# speedy_bldc.net
KiCad netlist of a schematic drawn in EAGLE
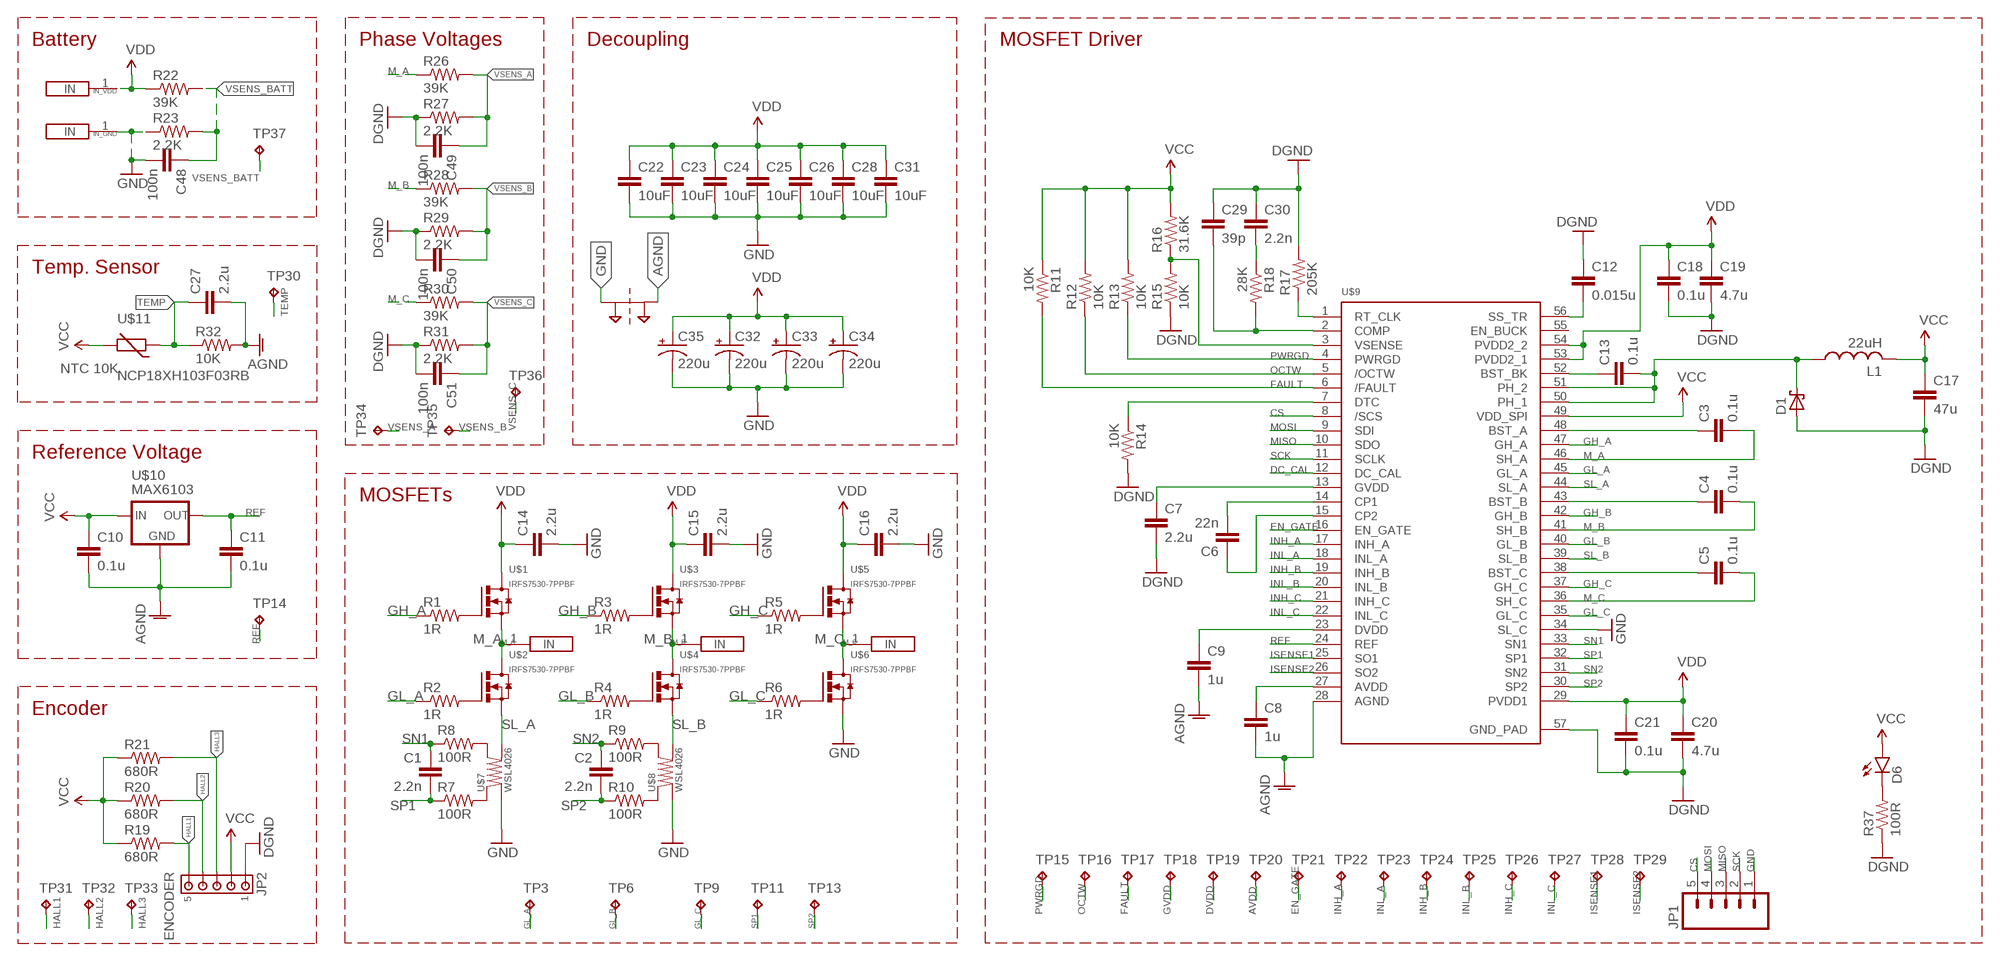
[diagram p0: schematic, sheet 1, part 1 of 2]
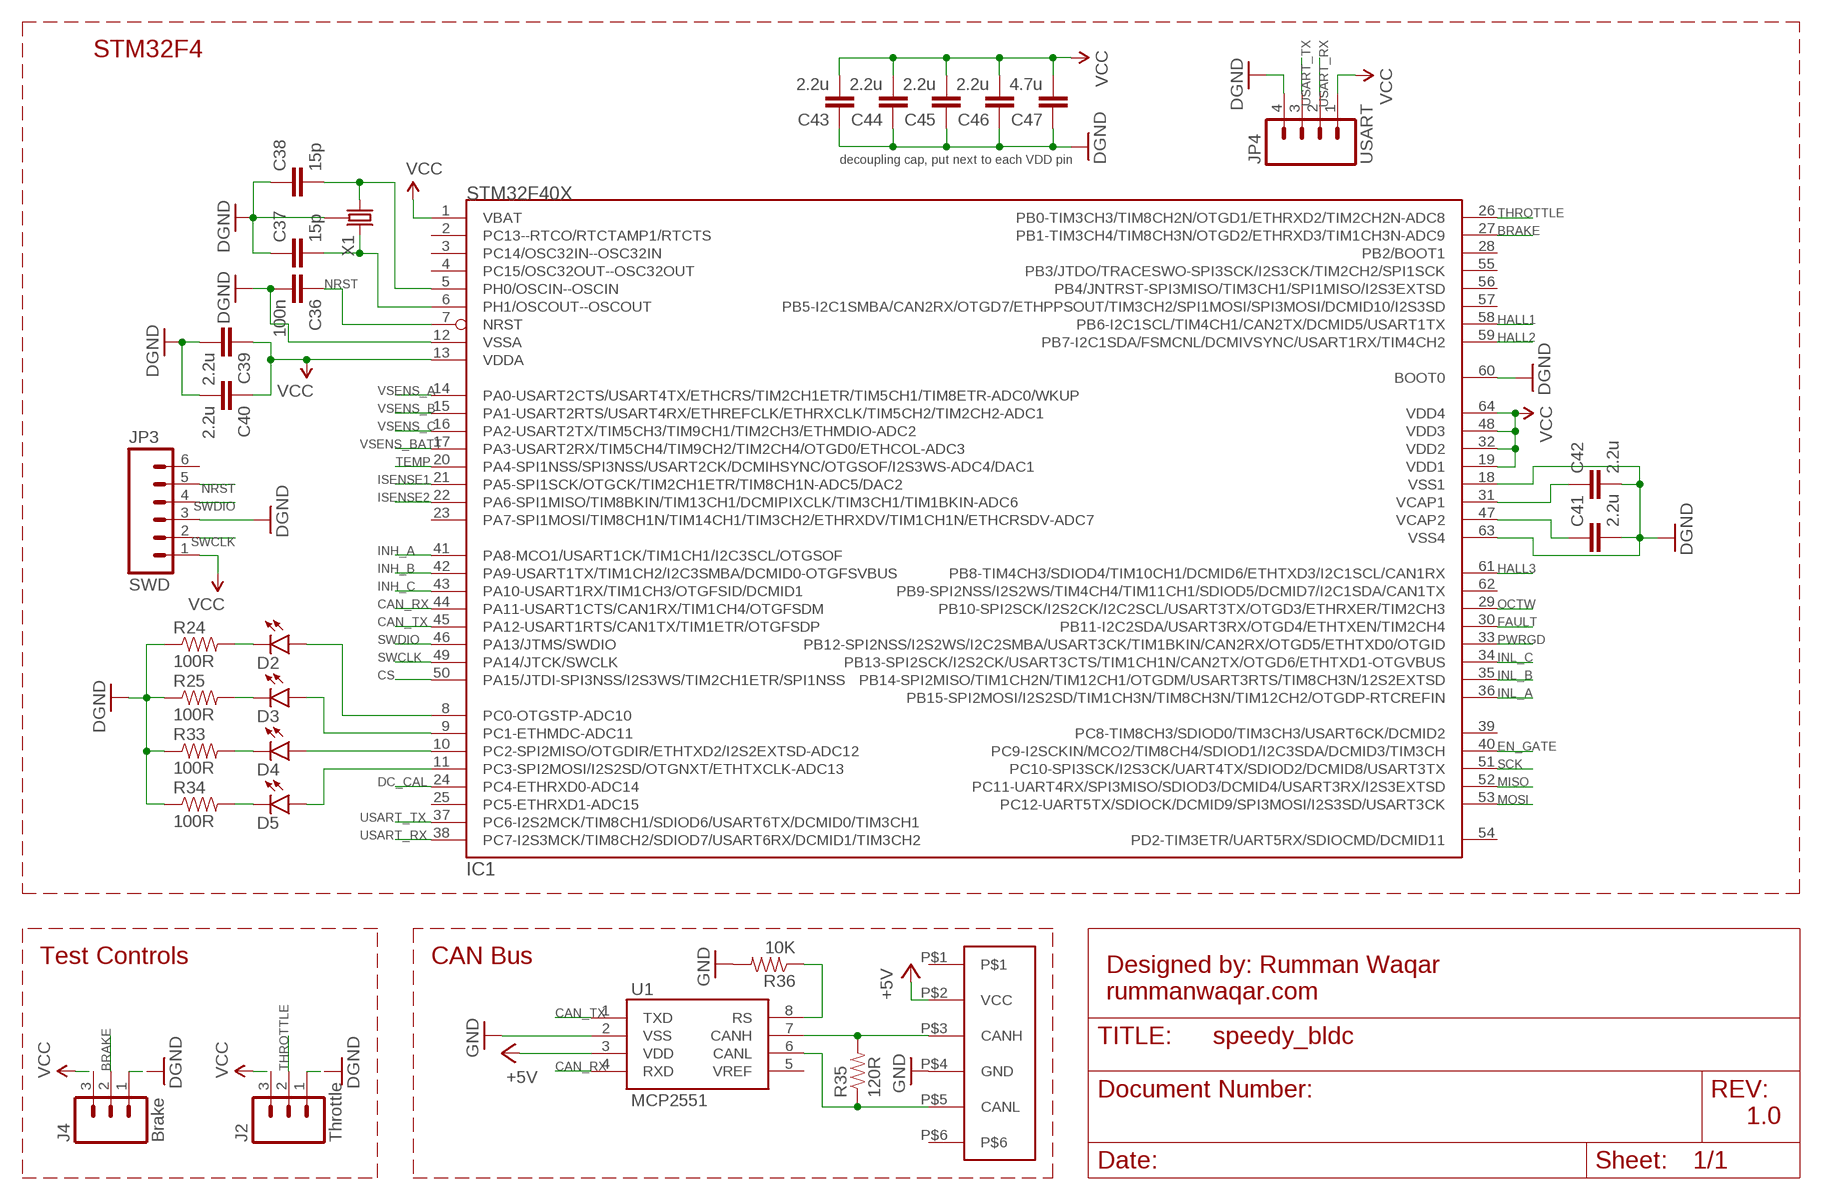
[diagram p1: schematic, sheet 1, part 2 of 2]

(export (version "E")
  (design (tool "Eeschema 10.0.6"))
  (components
    (comp (ref "C1")
      (value "2.2n")
      (footprint "eagle-import:0603-CAP")
      (fields (field (name "PARTNO") "399-7880-1-ND"))
      (libsource (lib "eagle-import") (part "CAP0603-CAP"))
    )
    (comp (ref "C2")
      (value "2.2n")
      (footprint "eagle-import:0603-CAP")
      (fields (field (name "PARTNO") "399-7880-1-ND"))
      (libsource (lib "eagle-import") (part "CAP0603-CAP"))
    )
    (comp (ref "C3")
      (value "0.1u")
      (footprint "eagle-import:0603-CAP")
      (fields (field (name "PARTNO") "399-7845-1-ND") (field (name "VOLTAGE") "16V"))
      (libsource (lib "eagle-import") (part "CAP0603-CAP"))
    )
    (comp (ref "C4")
      (value "0.1u")
      (footprint "eagle-import:0603-CAP")
      (fields (field (name "PARTNO") "399-7845-1-ND") (field (name "VOLTAGE") "16V"))
      (libsource (lib "eagle-import") (part "CAP0603-CAP"))
    )
    (comp (ref "C5")
      (value "0.1u")
      (footprint "eagle-import:0603-CAP")
      (fields (field (name "PARTNO") "399-7845-1-ND") (field (name "VOLTAGE") "16V"))
      (libsource (lib "eagle-import") (part "CAP0603-CAP"))
    )
    (comp (ref "C6")
      (value "22n")
      (footprint "eagle-import:0603-CAP")
      (fields (field (name "PARTNO") "1276-1936-1-ND") (field (name "VOLTAGE") "60V"))
      (libsource (lib "eagle-import") (part "CAP0603-CAP"))
    )
    (comp (ref "C7")
      (value "2.2u")
      (footprint "eagle-import:0603-CAP")
      (fields (field (name "PARTNO") "1276-1879-1-ND") (field (name "VOLTAGE") "16V"))
      (libsource (lib "eagle-import") (part "CAP0603-CAP"))
    )
    (comp (ref "C8")
      (value "1u")
      (footprint "eagle-import:0603-CAP")
      (fields (field (name "PARTNO") "587-2984-1-ND") (field (name "VOLTAGE") "10V"))
      (libsource (lib "eagle-import") (part "CAP0603-CAP"))
    )
    (comp (ref "C9")
      (value "1u")
      (footprint "eagle-import:0603-CAP")
      (fields (field (name "PARTNO") "587-2984-1-ND") (field (name "VOLTAGE") "6.3V"))
      (libsource (lib "eagle-import") (part "CAP0603-CAP"))
    )
    (comp (ref "C10")
      (value "0.1u")
      (footprint "eagle-import:0603-CAP")
      (fields (field (name "PARTNO") "399-7845-1-ND"))
      (libsource (lib "eagle-import") (part "CAP0603-CAP"))
    )
    (comp (ref "C11")
      (value "0.1u")
      (footprint "eagle-import:0603-CAP")
      (fields (field (name "PARTNO") "399-7845-1-ND"))
      (libsource (lib "eagle-import") (part "CAP0603-CAP"))
    )
    (comp (ref "C12")
      (value "0.015u")
      (footprint "eagle-import:0603-CAP")
      (fields (field (name "PARTNO") "587-1097-1-ND"))
      (libsource (lib "eagle-import") (part "CAP0603-CAP"))
    )
    (comp (ref "C13")
      (value "0.1u")
      (footprint "eagle-import:0603-CAP")
      (fields (field (name "PARTNO") "399-7845-1-ND"))
      (libsource (lib "eagle-import") (part "CAP0603-CAP"))
    )
    (comp (ref "C14")
      (value "2.2u")
      (footprint "eagle-import:1206-CAP")
      (fields (field (name "PARTNO") "445-5208-1-ND"))
      (libsource (lib "eagle-import") (part "2.2UF50V10%(1206)"))
    )
    (comp (ref "C15")
      (value "2.2u")
      (footprint "eagle-import:1206-CAP")
      (fields (field (name "PARTNO") "445-5208-1-ND"))
      (libsource (lib "eagle-import") (part "2.2UF50V10%(1206)"))
    )
    (comp (ref "C16")
      (value "2.2u")
      (footprint "eagle-import:1206-CAP")
      (fields (field (name "PARTNO") "445-5208-1-ND"))
      (libsource (lib "eagle-import") (part "2.2UF50V10%(1206)"))
    )
    (comp (ref "C17")
      (value "47u")
      (footprint "eagle-import:1206")
      (fields (field (name "PARTNO") "490-3907-1-ND"))
      (libsource (lib "eagle-import") (part "CAP1206"))
    )
    (comp (ref "C18")
      (value "0.1u")
      (footprint "eagle-import:0603-CAP")
      (fields (field (name "PARTNO") "399-7845-1-ND"))
      (libsource (lib "eagle-import") (part "CAP0603-CAP"))
    )
    (comp (ref "C19")
      (value "4.7u")
      (footprint "eagle-import:0805")
      (fields (field (name "PARTNO") "1276-1248-1-ND"))
      (libsource (lib "eagle-import") (part "CAP0805"))
    )
    (comp (ref "C20")
      (value "4.7u")
      (footprint "eagle-import:0805")
      (fields (field (name "PARTNO") "1276-1248-1-ND"))
      (libsource (lib "eagle-import") (part "CAP0805"))
    )
    (comp (ref "C21")
      (value "0.1u")
      (footprint "eagle-import:0603-CAP")
      (fields (field (name "PARTNO") "399-7845-1-ND"))
      (libsource (lib "eagle-import") (part "CAP0603-CAP"))
    )
    (comp (ref "C22")
      (value "10uF")
      (footprint "eagle-import:1206")
      (fields (field (name "PARTNO") "587-3248-1-ND"))
      (libsource (lib "eagle-import") (part "CAP1206"))
    )
    (comp (ref "C23")
      (value "10uF")
      (footprint "eagle-import:1206")
      (fields (field (name "PARTNO") "587-3248-1-ND"))
      (libsource (lib "eagle-import") (part "CAP1206"))
    )
    (comp (ref "C24")
      (value "10uF")
      (footprint "eagle-import:1206")
      (fields (field (name "PARTNO") "587-3248-1-ND"))
      (libsource (lib "eagle-import") (part "CAP1206"))
    )
    (comp (ref "C25")
      (value "10uF")
      (footprint "eagle-import:1206")
      (fields (field (name "PARTNO") "587-3248-1-ND"))
      (libsource (lib "eagle-import") (part "CAP1206"))
    )
    (comp (ref "C26")
      (value "10uF")
      (footprint "eagle-import:1206")
      (fields (field (name "PARTNO") "587-3248-1-ND"))
      (libsource (lib "eagle-import") (part "CAP1206"))
    )
    (comp (ref "C27")
      (value "2.2u")
      (footprint "eagle-import:0603-CAP")
      (fields (field (name "PARTNO") "1276-1879-1-ND"))
      (libsource (lib "eagle-import") (part "CAP0603-CAP"))
    )
    (comp (ref "C28")
      (value "10uF")
      (footprint "eagle-import:1206")
      (fields (field (name "PARTNO") "587-3248-1-ND"))
      (libsource (lib "eagle-import") (part "CAP1206"))
    )
    (comp (ref "C29")
      (value "39p")
      (footprint "eagle-import:0603-CAP")
      (fields (field (name "PARTNO") "712-1345-1-ND"))
      (libsource (lib "eagle-import") (part "CAP0603-CAP"))
    )
    (comp (ref "C30")
      (value "2.2n")
      (footprint "eagle-import:0603-CAP")
      (fields (field (name "PARTNO") "399-7880-1-ND"))
      (libsource (lib "eagle-import") (part "CAP0603-CAP"))
    )
    (comp (ref "C31")
      (value "10uF")
      (footprint "eagle-import:1206")
      (fields (field (name "PARTNO") "587-3248-1-ND"))
      (libsource (lib "eagle-import") (part "CAP1206"))
    )
    (comp (ref "C32")
      (value "220u")
      (footprint "eagle-import:E3,5-8")
      (fields (field (name "PARTNO") "493-11950-1-ND"))
      (libsource (lib "eagle-import") (part "CPOL-USE3.5-8"))
    )
    (comp (ref "C33")
      (value "220u")
      (footprint "eagle-import:E3,5-8")
      (fields (field (name "PARTNO") "493-11950-1-ND"))
      (libsource (lib "eagle-import") (part "CPOL-USE3.5-8"))
    )
    (comp (ref "C34")
      (value "220u")
      (footprint "eagle-import:E3,5-8")
      (fields (field (name "PARTNO") "493-11950-1-ND"))
      (libsource (lib "eagle-import") (part "CPOL-USE3.5-8"))
    )
    (comp (ref "C35")
      (value "220u")
      (footprint "eagle-import:E3,5-8")
      (fields (field (name "PARTNO") "493-11950-1-ND"))
      (libsource (lib "eagle-import") (part "CPOL-USE3.5-8"))
    )
    (comp (ref "C36")
      (value "100n")
      (footprint "eagle-import:0603-CAP")
      (fields (field (name "PARTNO") "399-1097-1-ND"))
      (libsource (lib "eagle-import") (part "CAP0603-CAP"))
    )
    (comp (ref "C37")
      (value "15p")
      (footprint "eagle-import:0603-CAP")
      (fields (field (name "PARTNO") "712-1318-1-ND"))
      (libsource (lib "eagle-import") (part "CAP0603-CAP"))
    )
    (comp (ref "C38")
      (value "15p")
      (footprint "eagle-import:0603-CAP")
      (fields (field (name "PARTNO") "712-1318-1-ND"))
      (libsource (lib "eagle-import") (part "CAP0603-CAP"))
    )
    (comp (ref "C39")
      (value "2.2u")
      (footprint "eagle-import:0603-CAP")
      (fields (field (name "PARTNO") "1276-1879-1-ND"))
      (libsource (lib "eagle-import") (part "CAP0603-CAP"))
    )
    (comp (ref "C40")
      (value "2.2u")
      (footprint "eagle-import:0603-CAP")
      (fields (field (name "PARTNO") "1276-1879-1-ND"))
      (libsource (lib "eagle-import") (part "CAP0603-CAP"))
    )
    (comp (ref "C41")
      (value "2.2u")
      (footprint "eagle-import:0603-CAP")
      (fields (field (name "PARTNO") "1276-1879-1-ND"))
      (libsource (lib "eagle-import") (part "CAP0603-CAP"))
    )
    (comp (ref "C42")
      (value "2.2u")
      (footprint "eagle-import:0603-CAP")
      (fields (field (name "PARTNO") "1276-1879-1-ND"))
      (libsource (lib "eagle-import") (part "CAP0603-CAP"))
    )
    (comp (ref "C43")
      (value "2.2u")
      (footprint "eagle-import:0603-CAP")
      (fields (field (name "PARTNO") "1276-1879-1-ND"))
      (libsource (lib "eagle-import") (part "CAP0603-CAP"))
    )
    (comp (ref "C44")
      (value "2.2u")
      (footprint "eagle-import:0603-CAP")
      (fields (field (name "PARTNO") "1276-1879-1-ND"))
      (libsource (lib "eagle-import") (part "CAP0603-CAP"))
    )
    (comp (ref "C45")
      (value "2.2u")
      (footprint "eagle-import:0603-CAP")
      (fields (field (name "PARTNO") "1276-1879-1-ND"))
      (libsource (lib "eagle-import") (part "CAP0603-CAP"))
    )
    (comp (ref "C46")
      (value "2.2u")
      (footprint "eagle-import:0603-CAP")
      (fields (field (name "PARTNO") "1276-1879-1-ND"))
      (libsource (lib "eagle-import") (part "CAP0603-CAP"))
    )
    (comp (ref "C47")
      (value "4.7u")
      (footprint "eagle-import:0603-CAP")
      (fields (field (name "PARTNO") "490-3302-1-ND"))
      (libsource (lib "eagle-import") (part "CAP0603-CAP"))
    )
    (comp (ref "C48")
      (value "100n")
      (footprint "eagle-import:0603-CAP")
      (fields (field (name "PARTNO") "399-1097-1-ND"))
      (libsource (lib "eagle-import") (part "CAP0603-CAP"))
    )
    (comp (ref "C49")
      (value "100n")
      (footprint "eagle-import:0603-CAP")
      (fields (field (name "PARTNO") "399-1097-1-ND"))
      (libsource (lib "eagle-import") (part "CAP0603-CAP"))
    )
    (comp (ref "C50")
      (value "100n")
      (footprint "eagle-import:0603-CAP")
      (fields (field (name "PARTNO") "399-1097-1-ND"))
      (libsource (lib "eagle-import") (part "CAP0603-CAP"))
    )
    (comp (ref "C51")
      (value "100n")
      (footprint "eagle-import:0603-CAP")
      (fields (field (name "PARTNO") "399-1097-1-ND"))
      (libsource (lib "eagle-import") (part "CAP0603-CAP"))
    )
    (comp (ref "D1")
      (value "SCHOTTKY_SMA")
      (footprint "eagle-import:SMA")
      (fields (field (name "PARTNO") "497-12285-1-ND"))
      (libsource (lib "eagle-import") (part "SCHOTTKY_SMA"))
    )
    (comp (ref "D2")
      (value "LED-FKIT-1206")
      (footprint "eagle-import:FKIT-LED-1206")
      (fields (field (name "PARTNO") "160-1457-1-ND"))
      (libsource (lib "eagle-import") (part "LED-FKIT-1206"))
    )
    (comp (ref "D3")
      (value "LED-FKIT-1206")
      (footprint "eagle-import:FKIT-LED-1206")
      (fields (field (name "PARTNO") "160-1457-1-ND"))
      (libsource (lib "eagle-import") (part "LED-FKIT-1206"))
    )
    (comp (ref "D4")
      (value "LED-FKIT-1206")
      (footprint "eagle-import:FKIT-LED-1206")
      (fields (field (name "PARTNO") "160-1457-1-ND"))
      (libsource (lib "eagle-import") (part "LED-FKIT-1206"))
    )
    (comp (ref "D5")
      (value "LED-FKIT-1206")
      (footprint "eagle-import:FKIT-LED-1206")
      (fields (field (name "PARTNO") "160-1457-1-ND"))
      (libsource (lib "eagle-import") (part "LED-FKIT-1206"))
    )
    (comp (ref "D6")
      (value "LED-FKIT-1206")
      (footprint "eagle-import:FKIT-LED-1206")
      (fields (field (name "PARTNO") "160-1457-1-ND"))
      (libsource (lib "eagle-import") (part "LED-FKIT-1206"))
    )
    (comp (ref "IC1")
      (value "STM32F40X")
      (footprint "eagle-import:LQFP64")
      (fields (field (name "PARTNO") "497-11767-ND"))
      (libsource (lib "eagle-import") (part "STM32F40X"))
    )
    (comp (ref "IN_GND")
      (value "1CONN")
      (footprint "eagle-import:1CONN")
      (libsource (lib "eagle-import") (part "1CONN"))
    )
    (comp (ref "IN_VDD")
      (value "1CONN")
      (footprint "eagle-import:1CONN")
      (libsource (lib "eagle-import") (part "1CONN"))
    )
    (comp (ref "J2")
      (value "Throttle")
      (footprint "eagle-import:1X03")
      (libsource (lib "eagle-import") (part "M03PTH"))
    )
    (comp (ref "J4")
      (value "Brake")
      (footprint "eagle-import:1X03")
      (libsource (lib "eagle-import") (part "M03PTH"))
    )
    (comp (ref "JP1")
      (value "M05NO_SILK")
      (footprint "eagle-import:1X05_NO_SILK")
      (libsource (lib "eagle-import") (part "M05NO_SILK"))
    )
    (comp (ref "JP2")
      (value "ENCODER")
      (footprint "eagle-import:1445055-5")
      (fields (field (name "PARTNO") "A33210-ND"))
      (libsource (lib "eagle-import") (part "1445055-5"))
    )
    (comp (ref "JP3")
      (value "SWD")
      (footprint "eagle-import:1X06_NO_SILK")
      (libsource (lib "eagle-import") (part "M06NO_SILK_FEMALE_PTH"))
    )
    (comp (ref "JP4")
      (value "USART")
      (footprint "eagle-import:1X04")
      (libsource (lib "eagle-import") (part "M04PTH"))
    )
    (comp (ref "L1")
      (value "22uH")
      (footprint "eagle-import:L5650M")
      (fields (field (name "PARTNO") "490-5272-1-ND"))
      (libsource (lib "eagle-import") (part "L-USL5650M"))
    )
    (comp (ref "M_A")
      (value "1CONN")
      (footprint "eagle-import:1CONN")
      (libsource (lib "eagle-import") (part "1CONN"))
    )
    (comp (ref "M_B")
      (value "1CONN")
      (footprint "eagle-import:1CONN")
      (libsource (lib "eagle-import") (part "1CONN"))
    )
    (comp (ref "M_C")
      (value "1CONN")
      (footprint "eagle-import:1CONN")
      (libsource (lib "eagle-import") (part "1CONN"))
    )
    (comp (ref "PT1")
      (value "2PT_GND_TIE")
      (footprint "eagle-import:2PT_GND_TIE")
      (libsource (lib "eagle-import") (part "2PT_GND_TIE"))
    )
    (comp (ref "R1")
      (value "1R")
      (footprint "eagle-import:0603-RES")
      (fields (field (name "PARTNO") "1276-4991-1-ND"))
      (libsource (lib "eagle-import") (part "RESISTOR0603"))
    )
    (comp (ref "R2")
      (value "1R")
      (footprint "eagle-import:0603-RES")
      (fields (field (name "PARTNO") "1276-4991-1-ND"))
      (libsource (lib "eagle-import") (part "RESISTOR0603"))
    )
    (comp (ref "R3")
      (value "1R")
      (footprint "eagle-import:0603-RES")
      (fields (field (name "PARTNO") "1276-4991-1-ND"))
      (libsource (lib "eagle-import") (part "RESISTOR0603"))
    )
    (comp (ref "R4")
      (value "1R")
      (footprint "eagle-import:0603-RES")
      (fields (field (name "PARTNO") "1276-4991-1-ND"))
      (libsource (lib "eagle-import") (part "RESISTOR0603"))
    )
    (comp (ref "R5")
      (value "1R")
      (footprint "eagle-import:0603-RES")
      (fields (field (name "PARTNO") "1276-4991-1-ND"))
      (libsource (lib "eagle-import") (part "RESISTOR0603"))
    )
    (comp (ref "R6")
      (value "1R")
      (footprint "eagle-import:0603-RES")
      (fields (field (name "PARTNO") "1276-4991-1-ND"))
      (libsource (lib "eagle-import") (part "RESISTOR0603"))
    )
    (comp (ref "R7")
      (value "100R")
      (footprint "eagle-import:0603-RES")
      (fields (field (name "PARTNO") "311-100HRCT-ND"))
      (libsource (lib "eagle-import") (part "RESISTOR0603"))
    )
    (comp (ref "R8")
      (value "100R")
      (footprint "eagle-import:0603-RES")
      (fields (field (name "PARTNO") "311-100HRCT-ND"))
      (libsource (lib "eagle-import") (part "RESISTOR0603"))
    )
    (comp (ref "R9")
      (value "100R")
      (footprint "eagle-import:0603-RES")
      (fields (field (name "PARTNO") "311-100HRCT-ND"))
      (libsource (lib "eagle-import") (part "RESISTOR0603"))
    )
    (comp (ref "R10")
      (value "100R")
      (footprint "eagle-import:0603-RES")
      (fields (field (name "PARTNO") "311-100HRCT-ND"))
      (libsource (lib "eagle-import") (part "RESISTOR0603"))
    )
    (comp (ref "R11")
      (value "10K")
      (footprint "eagle-import:0603-RES")
      (fields (field (name "PARTNO") "311-10KGRCT-ND"))
      (libsource (lib "eagle-import") (part "RESISTOR0603"))
    )
    (comp (ref "R12")
      (value "10K")
      (footprint "eagle-import:0603-RES")
      (fields (field (name "PARTNO") "311-10KGRCT-ND"))
      (libsource (lib "eagle-import") (part "RESISTOR0603"))
    )
    (comp (ref "R13")
      (value "10K")
      (footprint "eagle-import:0603-RES")
      (fields (field (name "PARTNO") "311-10KGRCT-ND"))
      (libsource (lib "eagle-import") (part "RESISTOR0603"))
    )
    (comp (ref "R14")
      (value "10K")
      (footprint "eagle-import:0603-RES")
      (fields (field (name "PARTNO") "311-10KGRCT-ND"))
      (libsource (lib "eagle-import") (part "RESISTOR0603"))
    )
    (comp (ref "R15")
      (value "10K")
      (footprint "eagle-import:0603-RES")
      (fields (field (name "PARTNO") "311-10KGRCT-ND"))
      (libsource (lib "eagle-import") (part "RESISTOR0603"))
    )
    (comp (ref "R16")
      (value "31.6K")
      (footprint "eagle-import:0603-RES")
      (fields (field (name "PARTNO") "311-31.6KHRCT-ND"))
      (libsource (lib "eagle-import") (part "RESISTOR0603"))
    )
    (comp (ref "R17")
      (value "205K")
      (footprint "eagle-import:0603-RES")
      (fields (field (name "PARTNO") "541-205KHCT-ND"))
      (libsource (lib "eagle-import") (part "RESISTOR0603"))
    )
    (comp (ref "R18")
      (value "28K")
      (footprint "eagle-import:0603-RES")
      (fields (field (name "PARTNO") "311-28.0KHRCT-ND"))
      (libsource (lib "eagle-import") (part "RESISTOR0603"))
    )
    (comp (ref "R19")
      (value "680R")
      (footprint "eagle-import:0603-RES")
      (fields (field (name "PARTNO") "311-680HRCT-ND"))
      (libsource (lib "eagle-import") (part "RESISTOR0603"))
    )
    (comp (ref "R20")
      (value "680R")
      (footprint "eagle-import:0603-RES")
      (fields (field (name "PARTNO") "311-680HRCT-ND"))
      (libsource (lib "eagle-import") (part "RESISTOR0603"))
    )
    (comp (ref "R21")
      (value "680R")
      (footprint "eagle-import:0603-RES")
      (fields (field (name "PARTNO") "311-680HRCT-ND"))
      (libsource (lib "eagle-import") (part "RESISTOR0603"))
    )
    (comp (ref "R22")
      (value "39K")
      (footprint "eagle-import:0603-RES")
      (fields (field (name "PARTNO") "311-39.0KHRCT-ND"))
      (libsource (lib "eagle-import") (part "RESISTOR0603-RES"))
    )
    (comp (ref "R23")
      (value "2.2K")
      (footprint "eagle-import:0603-RES")
      (fields (field (name "PARTNO") "311-2.20KHRCT-ND"))
      (libsource (lib "eagle-import") (part "RESISTOR0603-RES"))
    )
    (comp (ref "R24")
      (value "100R")
      (footprint "eagle-import:0603-RES")
      (fields (field (name "PARTNO") "311-100HRCT-ND"))
      (libsource (lib "eagle-import") (part "RESISTOR0603"))
    )
    (comp (ref "R25")
      (value "100R")
      (footprint "eagle-import:0603-RES")
      (fields (field (name "PARTNO") "311-100HRCT-ND"))
      (libsource (lib "eagle-import") (part "RESISTOR0603"))
    )
    (comp (ref "R26")
      (value "39K")
      (footprint "eagle-import:0603-RES")
      (fields (field (name "PARTNO") "311-39.0KHRCT-ND"))
      (libsource (lib "eagle-import") (part "RESISTOR0603-RES"))
    )
    (comp (ref "R27")
      (value "2.2K")
      (footprint "eagle-import:0603-RES")
      (fields (field (name "PARTNO") "311-2.20KHRCT-ND"))
      (libsource (lib "eagle-import") (part "RESISTOR0603-RES"))
    )
    (comp (ref "R28")
      (value "39K")
      (footprint "eagle-import:0603-RES")
      (fields (field (name "PARTNO") "311-39.0KHRCT-ND"))
      (libsource (lib "eagle-import") (part "RESISTOR0603-RES"))
    )
    (comp (ref "R29")
      (value "2.2K")
      (footprint "eagle-import:0603-RES")
      (fields (field (name "PARTNO") "311-2.20KHRCT-ND"))
      (libsource (lib "eagle-import") (part "RESISTOR0603-RES"))
    )
    (comp (ref "R30")
      (value "39K")
      (footprint "eagle-import:0603-RES")
      (fields (field (name "PARTNO") "311-39.0KHRCT-ND"))
      (libsource (lib "eagle-import") (part "RESISTOR0603-RES"))
    )
    (comp (ref "R31")
      (value "2.2K")
      (footprint "eagle-import:0603-RES")
      (fields (field (name "PARTNO") "311-2.20KHRCT-ND"))
      (libsource (lib "eagle-import") (part "RESISTOR0603-RES"))
    )
    (comp (ref "R32")
      (value "10K")
      (footprint "eagle-import:0603-RES")
      (fields (field (name "PARTNO") "RHM10.0KHCT-ND"))
      (libsource (lib "eagle-import") (part "RESISTOR0603"))
    )
    (comp (ref "R33")
      (value "100R")
      (footprint "eagle-import:0603-RES")
      (fields (field (name "PARTNO") "311-100HRCT-ND"))
      (libsource (lib "eagle-import") (part "RESISTOR0603"))
    )
    (comp (ref "R34")
      (value "100R")
      (footprint "eagle-import:0603-RES")
      (fields (field (name "PARTNO") "311-100HRCT-ND"))
      (libsource (lib "eagle-import") (part "RESISTOR0603"))
    )
    (comp (ref "R35")
      (value "120R")
      (footprint "eagle-import:0603-RES")
      (fields (field (name "PARTNO") "311-120GRCT-ND"))
      (libsource (lib "eagle-import") (part "RESISTOR0603"))
    )
    (comp (ref "R36")
      (value "10K")
      (footprint "eagle-import:0603-RES")
      (fields (field (name "PARTNO") "311-10KGRCT-ND"))
      (libsource (lib "eagle-import") (part "RESISTOR0603"))
    )
    (comp (ref "R37")
      (value "100R")
      (footprint "eagle-import:0603-RES")
      (fields (field (name "PARTNO") "311-100HRCT-ND"))
      (libsource (lib "eagle-import") (part "RESISTOR0603"))
    )
    (comp (ref "TP3")
      (value "TPB1,27")
      (footprint "eagle-import:B1,27")
      (libsource (lib "eagle-import") (part "TPB1,27"))
    )
    (comp (ref "TP6")
      (value "TPB1,27")
      (footprint "eagle-import:B1,27")
      (libsource (lib "eagle-import") (part "TPB1,27"))
    )
    (comp (ref "TP9")
      (value "TPB1,27")
      (footprint "eagle-import:B1,27")
      (libsource (lib "eagle-import") (part "TPB1,27"))
    )
    (comp (ref "TP11")
      (value "TPB1,27")
      (footprint "eagle-import:B1,27")
      (libsource (lib "eagle-import") (part "TPB1,27"))
    )
    (comp (ref "TP13")
      (value "TPB1,27")
      (footprint "eagle-import:B1,27")
      (libsource (lib "eagle-import") (part "TPB1,27"))
    )
    (comp (ref "TP14")
      (value "TPB1,27")
      (footprint "eagle-import:B1,27")
      (libsource (lib "eagle-import") (part "TPB1,27"))
    )
    (comp (ref "TP15")
      (value "TPB1,27")
      (footprint "eagle-import:B1,27")
      (libsource (lib "eagle-import") (part "TPB1,27"))
    )
    (comp (ref "TP16")
      (value "TPB1,27")
      (footprint "eagle-import:B1,27")
      (libsource (lib "eagle-import") (part "TPB1,27"))
    )
    (comp (ref "TP17")
      (value "TPB1,27")
      (footprint "eagle-import:B1,27")
      (libsource (lib "eagle-import") (part "TPB1,27"))
    )
    (comp (ref "TP18")
      (value "TPB1,27")
      (footprint "eagle-import:B1,27")
      (libsource (lib "eagle-import") (part "TPB1,27"))
    )
    (comp (ref "TP19")
      (value "TPB1,27")
      (footprint "eagle-import:B1,27")
      (libsource (lib "eagle-import") (part "TPB1,27"))
    )
    (comp (ref "TP20")
      (value "TPB1,27")
      (footprint "eagle-import:B1,27")
      (libsource (lib "eagle-import") (part "TPB1,27"))
    )
    (comp (ref "TP21")
      (value "TPB1,27")
      (footprint "eagle-import:B1,27")
      (libsource (lib "eagle-import") (part "TPB1,27"))
    )
    (comp (ref "TP22")
      (value "TPB1,27")
      (footprint "eagle-import:B1,27")
      (libsource (lib "eagle-import") (part "TPB1,27"))
    )
    (comp (ref "TP23")
      (value "TPB1,27")
      (footprint "eagle-import:B1,27")
      (libsource (lib "eagle-import") (part "TPB1,27"))
    )
    (comp (ref "TP24")
      (value "TPB1,27")
      (footprint "eagle-import:B1,27")
      (libsource (lib "eagle-import") (part "TPB1,27"))
    )
    (comp (ref "TP25")
      (value "TPB1,27")
      (footprint "eagle-import:B1,27")
      (libsource (lib "eagle-import") (part "TPB1,27"))
    )
    (comp (ref "TP26")
      (value "TPB1,27")
      (footprint "eagle-import:B1,27")
      (libsource (lib "eagle-import") (part "TPB1,27"))
    )
    (comp (ref "TP27")
      (value "TPB1,27")
      (footprint "eagle-import:B1,27")
      (libsource (lib "eagle-import") (part "TPB1,27"))
    )
    (comp (ref "TP28")
      (value "TPB1,27")
      (footprint "eagle-import:B1,27")
      (libsource (lib "eagle-import") (part "TPB1,27"))
    )
    (comp (ref "TP29")
      (value "TPB1,27")
      (footprint "eagle-import:B1,27")
      (libsource (lib "eagle-import") (part "TPB1,27"))
    )
    (comp (ref "TP30")
      (value "TPB1,27")
      (footprint "eagle-import:B1,27")
      (libsource (lib "eagle-import") (part "TPB1,27"))
    )
    (comp (ref "TP31")
      (value "TPB1,27")
      (footprint "eagle-import:B1,27")
      (libsource (lib "eagle-import") (part "TPB1,27"))
    )
    (comp (ref "TP32")
      (value "TPB1,27")
      (footprint "eagle-import:B1,27")
      (libsource (lib "eagle-import") (part "TPB1,27"))
    )
    (comp (ref "TP33")
      (value "TPB1,27")
      (footprint "eagle-import:B1,27")
      (libsource (lib "eagle-import") (part "TPB1,27"))
    )
    (comp (ref "TP34")
      (value "TPB1,27")
      (footprint "eagle-import:B1,27")
      (libsource (lib "eagle-import") (part "TPB1,27"))
    )
    (comp (ref "TP35")
      (value "TPB1,27")
      (footprint "eagle-import:B1,27")
      (libsource (lib "eagle-import") (part "TPB1,27"))
    )
    (comp (ref "TP36")
      (value "TPB1,27")
      (footprint "eagle-import:B1,27")
      (libsource (lib "eagle-import") (part "TPB1,27"))
    )
    (comp (ref "TP37")
      (value "TPB1,27")
      (footprint "eagle-import:B1,27")
      (libsource (lib "eagle-import") (part "TPB1,27"))
    )
    (comp (ref "U$1")
      (value "IRFS7530-7PPBF")
      (footprint "eagle-import:D2PAK-7PIN")
      (fields (field (name "PARTNO") "IRFS7530-7PPBF-ND"))
      (libsource (lib "eagle-import") (part "IRFS7530-7PPBF"))
    )
    (comp (ref "U$2")
      (value "IRFS7530-7PPBF")
      (footprint "eagle-import:D2PAK-7PIN")
      (fields (field (name "PARTNO") "IRFS7530-7PPBF-ND"))
      (libsource (lib "eagle-import") (part "IRFS7530-7PPBF"))
    )
    (comp (ref "U$3")
      (value "IRFS7530-7PPBF")
      (footprint "eagle-import:D2PAK-7PIN")
      (fields (field (name "PARTNO") "IRFS7530-7PPBF-ND"))
      (libsource (lib "eagle-import") (part "IRFS7530-7PPBF"))
    )
    (comp (ref "U$4")
      (value "IRFS7530-7PPBF")
      (footprint "eagle-import:D2PAK-7PIN")
      (fields (field (name "PARTNO") "IRFS7530-7PPBF-ND"))
      (libsource (lib "eagle-import") (part "IRFS7530-7PPBF"))
    )
    (comp (ref "U$5")
      (value "IRFS7530-7PPBF")
      (footprint "eagle-import:D2PAK-7PIN")
      (fields (field (name "PARTNO") "IRFS7530-7PPBF-ND"))
      (libsource (lib "eagle-import") (part "IRFS7530-7PPBF"))
    )
    (comp (ref "U$6")
      (value "IRFS7530-7PPBF")
      (footprint "eagle-import:D2PAK-7PIN")
      (fields (field (name "PARTNO") "IRFS7530-7PPBF-ND"))
      (libsource (lib "eagle-import") (part "IRFS7530-7PPBF"))
    )
    (comp (ref "U$7")
      (value "WSL4026")
      (footprint "eagle-import:WSL4026")
      (fields (field (name "PARTNO") "WSLR-.0003CT-ND"))
      (libsource (lib "eagle-import") (part "WSL4026"))
    )
    (comp (ref "U$8")
      (value "WSL4026")
      (footprint "eagle-import:WSL4026")
      (fields (field (name "PARTNO") "WSLR-.0003CT-ND"))
      (libsource (lib "eagle-import") (part "WSL4026"))
    )
    (comp (ref "U$9")
      (value "DRV8301")
      (footprint "eagle-import:56-TSSOP-POWERPAD")
      (fields (field (name "PARTNO") "296-29433-1-ND"))
      (libsource (lib "eagle-import") (part "DRV8301"))
    )
    (comp (ref "U$10")
      (value "MAX6103")
      (footprint "eagle-import:SOT23-3")
      (fields (field (name "PARTNO") "MAX6103EUR+TCT-ND"))
      (libsource (lib "eagle-import") (part "MAX6103"))
    )
    (comp (ref "U$11")
      (value "NCP18XH103F03RB")
      (footprint "eagle-import:R0603")
      (fields (field (name "PARTNO") "490-4800-1-ND"))
      (libsource (lib "eagle-import") (part "NCP18XH103F03RB"))
    )
    (comp (ref "U$12")
      (value "CAN_6P6C")
      (footprint "eagle-import:CAN_6P6C")
      (fields (field (name "PARTNO") "553-2258-ND"))
      (libsource (lib "eagle-import") (part "CAN_6P6C"))
    )
    (comp (ref "U1")
      (value "MCP2551")
      (footprint "eagle-import:SO08")
      (fields (field (name "PARTNO") "MCP2551T-E/SNCT-ND"))
      (libsource (lib "eagle-import") (part "MCP2551"))
    )
    (comp (ref "X1")
      (value "X1")
      (footprint "eagle-import:CRYSTAL-SMD-5X3")
      (fields (field (name "PARTNO") "535-9721-1-ND"))
      (libsource (lib "eagle-import") (part "CRYSTAL-GROUNDED"))
    )
  )
  (nets
    (net (code "1") (name "+5V") (class "Default")
      (node (ref "U$12") (pin "P$2") (pinfunction "VCC_P$2") (pintype "bidirectional"))
      (node (ref "U1") (pin "3") (pinfunction "VDD_3") (pintype "bidirectional"))
    )
    (net (code "2") (name "/AVDD") (class "Default")
      (node (ref "TP20") (pin "TP") (pinfunction "TP_TP") (pintype "input"))
    )
    (net (code "3") (name "/BRAKE") (class "Default")
      (node (ref "IC1") (pin "27") (pinfunction "PB1-TIM3CH4/TIM8CH3N/OTGD2/ETHRXD3/TIM1CH3N-ADC9_27") (pintype "bidirectional"))
      (node (ref "J4") (pin "2") (pinfunction "2_2") (pintype "passive"))
    )
    (net (code "4") (name "/CAN_RX") (class "Default")
      (node (ref "IC1") (pin "44") (pinfunction "PA11-USART1CTS/CAN1RX/TIM1CH4/OTGFSDM_44") (pintype "bidirectional"))
      (node (ref "U1") (pin "4") (pinfunction "RXD_4") (pintype "bidirectional"))
    )
    (net (code "5") (name "/CAN_TX") (class "Default")
      (node (ref "IC1") (pin "45") (pinfunction "PA12-USART1RTS/CAN1TX/TIM1ETR/OTGFSDP_45") (pintype "bidirectional"))
      (node (ref "U1") (pin "1") (pinfunction "TXD_1") (pintype "bidirectional"))
    )
    (net (code "6") (name "/CS") (class "Default")
      (node (ref "IC1") (pin "50") (pinfunction "PA15/JTDI-SPI3NSS/I2S3WS/TIM2CH1ETR/SPI1NSS_50") (pintype "bidirectional"))
      (node (ref "JP1") (pin "5") (pinfunction "5_5") (pintype "passive"))
      (node (ref "U$9") (pin "8") (pinfunction "/SCS_8") (pintype "bidirectional"))
    )
    (net (code "7") (name "/DC_CAL") (class "Default")
      (node (ref "IC1") (pin "24") (pinfunction "PC4-ETHRXD0-ADC14_24") (pintype "bidirectional"))
      (node (ref "U$9") (pin "12") (pinfunction "DC_CAL_12") (pintype "bidirectional"))
    )
    (net (code "8") (name "/DVDD") (class "Default")
      (node (ref "TP19") (pin "TP") (pinfunction "TP_TP") (pintype "input"))
    )
    (net (code "9") (name "/EN_GATE") (class "Default")
      (node (ref "IC1") (pin "40") (pinfunction "PC9-I2SCKIN/MCO2/TIM8CH4/SDIOD1/I2C3SDA/DCMID3/TIM3CH_40") (pintype "bidirectional"))
      (node (ref "TP21") (pin "TP") (pinfunction "TP_TP") (pintype "input"))
      (node (ref "U$9") (pin "16") (pinfunction "EN_GATE_16") (pintype "bidirectional"))
    )
    (net (code "10") (name "/FAULT") (class "Default")
      (node (ref "IC1") (pin "30") (pinfunction "PB11-I2C2SDA/USART3RX/OTGD4/ETHTXEN/TIM2CH4_30") (pintype "bidirectional"))
      (node (ref "R11") (pin "2") (pinfunction "2_2") (pintype "passive"))
      (node (ref "TP17") (pin "TP") (pinfunction "TP_TP") (pintype "input"))
      (node (ref "U$9") (pin "6") (pinfunction "/FAULT_6") (pintype "bidirectional"))
    )
    (net (code "11") (name "/GH_A") (class "Default")
      (node (ref "R1") (pin "1") (pinfunction "1_1") (pintype "passive"))
      (node (ref "U$9") (pin "47") (pinfunction "GH_A_47") (pintype "bidirectional"))
    )
    (net (code "12") (name "/GH_B") (class "Default")
      (node (ref "R3") (pin "1") (pinfunction "1_1") (pintype "passive"))
      (node (ref "U$9") (pin "42") (pinfunction "GH_B_42") (pintype "bidirectional"))
    )
    (net (code "13") (name "/GH_C") (class "Default")
      (node (ref "R5") (pin "1") (pinfunction "1_1") (pintype "passive"))
      (node (ref "U$9") (pin "37") (pinfunction "GH_C_37") (pintype "bidirectional"))
    )
    (net (code "14") (name "/GL_A") (class "Default")
      (node (ref "R2") (pin "1") (pinfunction "1_1") (pintype "passive"))
      (node (ref "TP3") (pin "TP") (pinfunction "TP_TP") (pintype "input"))
      (node (ref "U$9") (pin "45") (pinfunction "GL_A_45") (pintype "bidirectional"))
    )
    (net (code "15") (name "/GL_B") (class "Default")
      (node (ref "R4") (pin "1") (pinfunction "1_1") (pintype "passive"))
      (node (ref "TP6") (pin "TP") (pinfunction "TP_TP") (pintype "input"))
      (node (ref "U$9") (pin "40") (pinfunction "GL_B_40") (pintype "bidirectional"))
    )
    (net (code "16") (name "/GL_C") (class "Default")
      (node (ref "R6") (pin "1") (pinfunction "1_1") (pintype "passive"))
      (node (ref "TP9") (pin "TP") (pinfunction "TP_TP") (pintype "input"))
      (node (ref "U$9") (pin "35") (pinfunction "GL_C_35") (pintype "bidirectional"))
    )
    (net (code "17") (name "/GVDD") (class "Default")
      (node (ref "TP18") (pin "TP") (pinfunction "TP_TP") (pintype "input"))
    )
    (net (code "18") (name "/INH_A") (class "Default")
      (node (ref "IC1") (pin "41") (pinfunction "PA8-MCO1/USART1CK/TIM1CH1/I2C3SCL/OTGSOF_41") (pintype "bidirectional"))
      (node (ref "TP22") (pin "TP") (pinfunction "TP_TP") (pintype "input"))
      (node (ref "U$9") (pin "17") (pinfunction "INH_A_17") (pintype "bidirectional"))
    )
    (net (code "19") (name "/INH_B") (class "Default")
      (node (ref "IC1") (pin "42") (pinfunction "PA9-USART1TX/TIM1CH2/I2C3SMBA/DCMID0-OTGFSVBUS_42") (pintype "bidirectional"))
      (node (ref "TP24") (pin "TP") (pinfunction "TP_TP") (pintype "input"))
      (node (ref "U$9") (pin "19") (pinfunction "INH_B_19") (pintype "bidirectional"))
    )
    (net (code "20") (name "/INH_C") (class "Default")
      (node (ref "IC1") (pin "43") (pinfunction "PA10-USART1RX/TIM1CH3/OTGFSID/DCMID1_43") (pintype "bidirectional"))
      (node (ref "TP26") (pin "TP") (pinfunction "TP_TP") (pintype "input"))
      (node (ref "U$9") (pin "21") (pinfunction "INH_C_21") (pintype "bidirectional"))
    )
    (net (code "21") (name "/INL_A") (class "Default")
      (node (ref "IC1") (pin "36") (pinfunction "PB15-SPI2MOSI/I2S2SD/TIM1CH3N/TIM8CH3N/TIM12CH2/OTGDP-RTCREFIN_36") (pintype "bidirectional"))
      (node (ref "TP23") (pin "TP") (pinfunction "TP_TP") (pintype "input"))
      (node (ref "U$9") (pin "18") (pinfunction "INL_A_18") (pintype "bidirectional"))
    )
    (net (code "22") (name "/INL_B") (class "Default")
      (node (ref "IC1") (pin "35") (pinfunction "PB14-SPI2MISO/TIM1CH2N/TIM12CH1/OTGDM/USART3RTS/TIM8CH3N/12S2EXTSD_35") (pintype "bidirectional"))
      (node (ref "TP25") (pin "TP") (pinfunction "TP_TP") (pintype "input"))
      (node (ref "U$9") (pin "20") (pinfunction "INL_B_20") (pintype "bidirectional"))
    )
    (net (code "23") (name "/INL_C") (class "Default")
      (node (ref "IC1") (pin "34") (pinfunction "PB13-SPI2SCK/I2S2CK/USART3CTS/TIM1CH1N/CAN2TX/OTGD6/ETHTXD1-OTGVBUS_34") (pintype "bidirectional"))
      (node (ref "TP27") (pin "TP") (pinfunction "TP_TP") (pintype "input"))
      (node (ref "U$9") (pin "22") (pinfunction "INL_C_22") (pintype "bidirectional"))
    )
    (net (code "24") (name "/ISENSE1") (class "Default")
      (node (ref "IC1") (pin "21") (pinfunction "PA5-SPI1SCK/OTGCK/TIM2CH1ETR/TIM8CH1N-ADC5/DAC2_21") (pintype "bidirectional"))
      (node (ref "TP28") (pin "TP") (pinfunction "TP_TP") (pintype "input"))
      (node (ref "U$9") (pin "25") (pinfunction "SO1_25") (pintype "bidirectional"))
    )
    (net (code "25") (name "/ISENSE2") (class "Default")
      (node (ref "IC1") (pin "22") (pinfunction "PA6-SPI1MISO/TIM8BKIN/TIM13CH1/DCMIPIXCLK/TIM3CH1/TIM1BKIN-ADC6_22") (pintype "bidirectional"))
      (node (ref "TP29") (pin "TP") (pinfunction "TP_TP") (pintype "input"))
      (node (ref "U$9") (pin "26") (pinfunction "SO2_26") (pintype "bidirectional"))
    )
    (net (code "26") (name "/MISO") (class "Default")
      (node (ref "IC1") (pin "52") (pinfunction "PC11-UART4RX/SPI3MISO/SDIOD3/DCMID4/USART3RX/I2S3EXTSD_52") (pintype "bidirectional"))
      (node (ref "JP1") (pin "3") (pinfunction "3_3") (pintype "passive"))
      (node (ref "U$9") (pin "10") (pinfunction "SDO_10") (pintype "bidirectional"))
    )
    (net (code "27") (name "/MOSI") (class "Default")
      (node (ref "IC1") (pin "53") (pinfunction "PC12-UART5TX/SDIOCK/DCMID9/SPI3MOSI/I2S3SD/USART3CK_53") (pintype "bidirectional"))
      (node (ref "JP1") (pin "4") (pinfunction "4_4") (pintype "passive"))
      (node (ref "U$9") (pin "9") (pinfunction "SDI_9") (pintype "bidirectional"))
    )
    (net (code "28") (name "/M_A") (class "Default")
      (node (ref "C3") (pin "2") (pinfunction "2_2") (pintype "passive"))
      (node (ref "M_A") (pin "1") (pinfunction "IN_1") (pintype "bidirectional"))
      (node (ref "R26") (pin "1") (pinfunction "1_1") (pintype "passive"))
      (node (ref "U$1") (pin "S") (pinfunction "S_S") (pintype "passive"))
      (node (ref "U$1") (pin "S1") (pinfunction "S_S1") (pintype "passive"))
      (node (ref "U$1") (pin "S2") (pinfunction "S_S2") (pintype "passive"))
      (node (ref "U$1") (pin "S3") (pinfunction "S_S3") (pintype "passive"))
      (node (ref "U$1") (pin "S4") (pinfunction "S_S4") (pintype "passive"))
      (node (ref "U$2") (pin "D") (pinfunction "D_D") (pintype "passive"))
      (node (ref "U$9") (pin "46") (pinfunction "SH_A_46") (pintype "bidirectional"))
    )
    (net (code "29") (name "/M_B") (class "Default")
      (node (ref "C4") (pin "2") (pinfunction "2_2") (pintype "passive"))
      (node (ref "M_B") (pin "1") (pinfunction "IN_1") (pintype "bidirectional"))
      (node (ref "R28") (pin "1") (pinfunction "1_1") (pintype "passive"))
      (node (ref "U$3") (pin "S") (pinfunction "S_S") (pintype "passive"))
      (node (ref "U$3") (pin "S1") (pinfunction "S_S1") (pintype "passive"))
      (node (ref "U$3") (pin "S2") (pinfunction "S_S2") (pintype "passive"))
      (node (ref "U$3") (pin "S3") (pinfunction "S_S3") (pintype "passive"))
      (node (ref "U$3") (pin "S4") (pinfunction "S_S4") (pintype "passive"))
      (node (ref "U$4") (pin "D") (pinfunction "D_D") (pintype "passive"))
      (node (ref "U$9") (pin "41") (pinfunction "SH_B_41") (pintype "bidirectional"))
    )
    (net (code "30") (name "/M_C") (class "Default")
      (node (ref "C5") (pin "2") (pinfunction "2_2") (pintype "passive"))
      (node (ref "M_C") (pin "1") (pinfunction "IN_1") (pintype "bidirectional"))
      (node (ref "R30") (pin "1") (pinfunction "1_1") (pintype "passive"))
      (node (ref "U$5") (pin "S") (pinfunction "S_S") (pintype "passive"))
      (node (ref "U$5") (pin "S1") (pinfunction "S_S1") (pintype "passive"))
      (node (ref "U$5") (pin "S2") (pinfunction "S_S2") (pintype "passive"))
      (node (ref "U$5") (pin "S3") (pinfunction "S_S3") (pintype "passive"))
      (node (ref "U$5") (pin "S4") (pinfunction "S_S4") (pintype "passive"))
      (node (ref "U$6") (pin "D") (pinfunction "D_D") (pintype "passive"))
      (node (ref "U$9") (pin "36") (pinfunction "SH_C_36") (pintype "bidirectional"))
    )
    (net (code "31") (name "/NRST") (class "Default")
      (node (ref "C36") (pin "1") (pinfunction "1_1") (pintype "passive"))
      (node (ref "IC1") (pin "7") (pinfunction "NRST_7") (pintype "bidirectional"))
      (node (ref "JP3") (pin "5") (pinfunction "5_5") (pintype "passive"))
    )
    (net (code "32") (name "/OCTW") (class "Default")
      (node (ref "IC1") (pin "29") (pinfunction "PB10-SPI2SCK/I2S2CK/I2C2SCL/USART3TX/OTGD3/ETHRXER/TIM2CH3_29") (pintype "bidirectional"))
      (node (ref "R12") (pin "1") (pinfunction "1_1") (pintype "passive"))
      (node (ref "TP16") (pin "TP") (pinfunction "TP_TP") (pintype "input"))
      (node (ref "U$9") (pin "5") (pinfunction "/OCTW_5") (pintype "bidirectional"))
    )
    (net (code "33") (name "/PWRGD") (class "Default")
      (node (ref "IC1") (pin "33") (pinfunction "PB12-SPI2NSS/I2S2WS/I2C2SMBA/USART3CK/TIM1BKIN/CAN2RX/OTGD5/ETHTXD0/OTGID_33") (pintype "bidirectional"))
      (node (ref "R13") (pin "1") (pinfunction "1_1") (pintype "passive"))
      (node (ref "TP15") (pin "TP") (pinfunction "TP_TP") (pintype "input"))
      (node (ref "U$9") (pin "4") (pinfunction "PWRGD_4") (pintype "bidirectional"))
    )
    (net (code "34") (name "/REF") (class "Default")
      (node (ref "C11") (pin "1") (pinfunction "1_1") (pintype "passive"))
      (node (ref "TP14") (pin "TP") (pinfunction "TP_TP") (pintype "input"))
      (node (ref "U$10") (pin "2") (pinfunction "OUT_2") (pintype "output"))
      (node (ref "U$9") (pin "24") (pinfunction "REF_24") (pintype "bidirectional"))
    )
    (net (code "35") (name "/SCK") (class "Default")
      (node (ref "IC1") (pin "51") (pinfunction "PC10-SPI3SCK/I2S3CK/UART4TX/SDIOD2/DCMID8/USART3TX_51") (pintype "bidirectional"))
      (node (ref "JP1") (pin "2") (pinfunction "2_2") (pintype "passive"))
      (node (ref "U$9") (pin "11") (pinfunction "SCLK_11") (pintype "bidirectional"))
    )
    (net (code "36") (name "/SL_A") (class "Default")
      (node (ref "U$2") (pin "S") (pinfunction "S_S") (pintype "passive"))
      (node (ref "U$2") (pin "S1") (pinfunction "S_S1") (pintype "passive"))
      (node (ref "U$2") (pin "S2") (pinfunction "S_S2") (pintype "passive"))
      (node (ref "U$2") (pin "S3") (pinfunction "S_S3") (pintype "passive"))
      (node (ref "U$2") (pin "S4") (pinfunction "S_S4") (pintype "passive"))
      (node (ref "U$7") (pin "P$1") (pinfunction "P$1_P$1") (pintype "bidirectional"))
      (node (ref "U$9") (pin "44") (pinfunction "SL_A_44") (pintype "bidirectional"))
    )
    (net (code "37") (name "/SL_B") (class "Default")
      (node (ref "U$4") (pin "S") (pinfunction "S_S") (pintype "passive"))
      (node (ref "U$4") (pin "S1") (pinfunction "S_S1") (pintype "passive"))
      (node (ref "U$4") (pin "S2") (pinfunction "S_S2") (pintype "passive"))
      (node (ref "U$4") (pin "S3") (pinfunction "S_S3") (pintype "passive"))
      (node (ref "U$4") (pin "S4") (pinfunction "S_S4") (pintype "passive"))
      (node (ref "U$8") (pin "P$1") (pinfunction "P$1_P$1") (pintype "bidirectional"))
      (node (ref "U$9") (pin "39") (pinfunction "SL_B_39") (pintype "bidirectional"))
    )
    (net (code "38") (name "/SN1") (class "Default")
      (node (ref "C1") (pin "1") (pinfunction "1_1") (pintype "passive"))
      (node (ref "R8") (pin "1") (pinfunction "1_1") (pintype "passive"))
      (node (ref "U$9") (pin "33") (pinfunction "SN1_33") (pintype "bidirectional"))
    )
    (net (code "39") (name "/SN2") (class "Default")
      (node (ref "C2") (pin "1") (pinfunction "1_1") (pintype "passive"))
      (node (ref "R9") (pin "1") (pinfunction "1_1") (pintype "passive"))
      (node (ref "U$9") (pin "31") (pinfunction "SN2_31") (pintype "bidirectional"))
    )
    (net (code "40") (name "/SP1") (class "Default")
      (node (ref "C1") (pin "2") (pinfunction "2_2") (pintype "passive"))
      (node (ref "R7") (pin "1") (pinfunction "1_1") (pintype "passive"))
      (node (ref "TP11") (pin "TP") (pinfunction "TP_TP") (pintype "input"))
      (node (ref "U$9") (pin "32") (pinfunction "SP1_32") (pintype "bidirectional"))
    )
    (net (code "41") (name "/SP2") (class "Default")
      (node (ref "C2") (pin "2") (pinfunction "2_2") (pintype "passive"))
      (node (ref "R10") (pin "1") (pinfunction "1_1") (pintype "passive"))
      (node (ref "TP13") (pin "TP") (pinfunction "TP_TP") (pintype "input"))
      (node (ref "U$9") (pin "30") (pinfunction "SP2_30") (pintype "bidirectional"))
    )
    (net (code "42") (name "/SWCLK") (class "Default")
      (node (ref "IC1") (pin "49") (pinfunction "PA14/JTCK/SWCLK_49") (pintype "bidirectional"))
      (node (ref "JP3") (pin "2") (pinfunction "2_2") (pintype "passive"))
    )
    (net (code "43") (name "/SWDIO") (class "Default")
      (node (ref "IC1") (pin "46") (pinfunction "PA13/JTMS/SWDIO_46") (pintype "bidirectional"))
      (node (ref "JP3") (pin "4") (pinfunction "4_4") (pintype "passive"))
    )
    (net (code "44") (name "/THROTTLE") (class "Default")
      (node (ref "IC1") (pin "26") (pinfunction "PB0-TIM3CH3/TIM8CH2N/OTGD1/ETHRXD2/TIM2CH2N-ADC8_26") (pintype "bidirectional"))
      (node (ref "J2") (pin "2") (pinfunction "2_2") (pintype "passive"))
    )
    (net (code "45") (name "/USART_RX") (class "Default")
      (node (ref "IC1") (pin "38") (pinfunction "PC7-I2S3MCK/TIM8CH2/SDIOD7/USART6RX/DCMID1/TIM3CH2_38") (pintype "bidirectional"))
      (node (ref "JP4") (pin "2") (pinfunction "2_2") (pintype "passive"))
    )
    (net (code "46") (name "/USART_TX") (class "Default")
      (node (ref "IC1") (pin "37") (pinfunction "PC6-I2S2MCK/TIM8CH1/SDIOD6/USART6TX/DCMID0/TIM3CH1_37") (pintype "bidirectional"))
      (node (ref "JP4") (pin "3") (pinfunction "3_3") (pintype "passive"))
    )
    (net (code "47") (name "AGND") (class "Default")
      (node (ref "C10") (pin "2") (pinfunction "2_2") (pintype "passive"))
      (node (ref "C11") (pin "2") (pinfunction "2_2") (pintype "passive"))
      (node (ref "C27") (pin "2") (pinfunction "2_2") (pintype "passive"))
      (node (ref "C8") (pin "2") (pinfunction "2_2") (pintype "passive"))
      (node (ref "C9") (pin "2") (pinfunction "2_2") (pintype "passive"))
      (node (ref "PT1") (pin "P$2") (pinfunction "P$2_P$2") (pintype "bidirectional"))
      (node (ref "R32") (pin "2") (pinfunction "2_2") (pintype "passive"))
      (node (ref "U$10") (pin "3") (pinfunction "GND_3") (pintype "input"))
      (node (ref "U$9") (pin "28") (pinfunction "AGND_28") (pintype "bidirectional"))
    )
    (net (code "48") (name "GND") (class "Default")
      (node (ref "C12") (pin "1") (pinfunction "1_1") (pintype "passive"))
      (node (ref "C14") (pin "2") (pinfunction "2_2") (pintype "passive"))
      (node (ref "C15") (pin "2") (pinfunction "2_2") (pintype "passive"))
      (node (ref "C16") (pin "2") (pinfunction "2_2") (pintype "passive"))
      (node (ref "C17") (pin "2") (pinfunction "2_2") (pintype "passive"))
      (node (ref "C18") (pin "2") (pinfunction "2_2") (pintype "passive"))
      (node (ref "C19") (pin "2") (pinfunction "2_2") (pintype "passive"))
      (node (ref "C20") (pin "2") (pinfunction "2_2") (pintype "passive"))
      (node (ref "C21") (pin "2") (pinfunction "2_2") (pintype "passive"))
      (node (ref "C22") (pin "2") (pinfunction "2_2") (pintype "passive"))
      (node (ref "C23") (pin "2") (pinfunction "2_2") (pintype "passive"))
      (node (ref "C24") (pin "2") (pinfunction "2_2") (pintype "passive"))
      (node (ref "C25") (pin "2") (pinfunction "2_2") (pintype "passive"))
      (node (ref "C26") (pin "2") (pinfunction "2_2") (pintype "passive"))
      (node (ref "C28") (pin "2") (pinfunction "2_2") (pintype "passive"))
      (node (ref "C29") (pin "1") (pinfunction "1_1") (pintype "passive"))
      (node (ref "C30") (pin "1") (pinfunction "1_1") (pintype "passive"))
      (node (ref "C31") (pin "2") (pinfunction "2_2") (pintype "passive"))
      (node (ref "C32") (pin "-") (pinfunction "-_-") (pintype "passive"))
      (node (ref "C33") (pin "-") (pinfunction "-_-") (pintype "passive"))
      (node (ref "C34") (pin "-") (pinfunction "-_-") (pintype "passive"))
      (node (ref "C35") (pin "-") (pinfunction "-_-") (pintype "passive"))
      (node (ref "C36") (pin "2") (pinfunction "2_2") (pintype "passive"))
      (node (ref "C37") (pin "1") (pinfunction "1_1") (pintype "passive"))
      (node (ref "C38") (pin "1") (pinfunction "1_1") (pintype "passive"))
      (node (ref "C39") (pin "2") (pinfunction "2_2") (pintype "passive"))
      (node (ref "C40") (pin "2") (pinfunction "2_2") (pintype "passive"))
      (node (ref "C41") (pin "2") (pinfunction "2_2") (pintype "passive"))
      (node (ref "C42") (pin "2") (pinfunction "2_2") (pintype "passive"))
      (node (ref "C43") (pin "1") (pinfunction "1_1") (pintype "passive"))
      (node (ref "C44") (pin "1") (pinfunction "1_1") (pintype "passive"))
      (node (ref "C45") (pin "1") (pinfunction "1_1") (pintype "passive"))
      (node (ref "C46") (pin "1") (pinfunction "1_1") (pintype "passive"))
      (node (ref "C47") (pin "1") (pinfunction "1_1") (pintype "passive"))
      (node (ref "C48") (pin "2") (pinfunction "2_2") (pintype "passive"))
      (node (ref "C49") (pin "2") (pinfunction "2_2") (pintype "passive"))
      (node (ref "C50") (pin "2") (pinfunction "2_2") (pintype "passive"))
      (node (ref "C51") (pin "2") (pinfunction "2_2") (pintype "passive"))
      (node (ref "C7") (pin "2") (pinfunction "2_2") (pintype "passive"))
      (node (ref "D1") (pin "A") (pinfunction "A_A") (pintype "passive"))
      (node (ref "IC1") (pin "12") (pinfunction "VSSA_12") (pintype "power_in"))
      (node (ref "IC1") (pin "18") (pinfunction "VSS1_18") (pintype "power_in"))
      (node (ref "IC1") (pin "60") (pinfunction "BOOT0_60") (pintype "input"))
      (node (ref "IC1") (pin "63") (pinfunction "VSS4_63") (pintype "bidirectional"))
      (node (ref "IN_GND") (pin "1") (pinfunction "IN_1") (pintype "bidirectional"))
      (node (ref "J2") (pin "1") (pinfunction "1_1") (pintype "passive"))
      (node (ref "J4") (pin "1") (pinfunction "1_1") (pintype "passive"))
      (node (ref "JP1") (pin "1") (pinfunction "1_1") (pintype "passive"))
      (node (ref "JP2") (pin "1") (pinfunction "1_1") (pintype "passive"))
      (node (ref "JP3") (pin "3") (pinfunction "3_3") (pintype "passive"))
      (node (ref "JP4") (pin "4") (pinfunction "4_4") (pintype "passive"))
      (node (ref "PT1") (pin "P$1") (pinfunction "P$1_P$1") (pintype "bidirectional"))
      (node (ref "R14") (pin "2") (pinfunction "2_2") (pintype "passive"))
      (node (ref "R15") (pin "1") (pinfunction "1_1") (pintype "passive"))
      (node (ref "R17") (pin "2") (pinfunction "2_2") (pintype "passive"))
      (node (ref "R23") (pin "1") (pinfunction "1_1") (pintype "passive"))
      (node (ref "R24") (pin "1") (pinfunction "1_1") (pintype "passive"))
      (node (ref "R25") (pin "1") (pinfunction "1_1") (pintype "passive"))
      (node (ref "R27") (pin "1") (pinfunction "1_1") (pintype "passive"))
      (node (ref "R29") (pin "1") (pinfunction "1_1") (pintype "passive"))
      (node (ref "R31") (pin "1") (pinfunction "1_1") (pintype "passive"))
      (node (ref "R33") (pin "1") (pinfunction "1_1") (pintype "passive"))
      (node (ref "R34") (pin "1") (pinfunction "1_1") (pintype "passive"))
      (node (ref "R36") (pin "2") (pinfunction "2_2") (pintype "passive"))
      (node (ref "R37") (pin "1") (pinfunction "1_1") (pintype "passive"))
      (node (ref "U$12") (pin "P$4") (pinfunction "GND_P$4") (pintype "bidirectional"))
      (node (ref "U$6") (pin "S") (pinfunction "S_S") (pintype "passive"))
      (node (ref "U$6") (pin "S1") (pinfunction "S_S1") (pintype "passive"))
      (node (ref "U$6") (pin "S2") (pinfunction "S_S2") (pintype "passive"))
      (node (ref "U$6") (pin "S3") (pinfunction "S_S3") (pintype "passive"))
      (node (ref "U$6") (pin "S4") (pinfunction "S_S4") (pintype "passive"))
      (node (ref "U$7") (pin "P$2") (pinfunction "P$2_P$2") (pintype "bidirectional"))
      (node (ref "U$8") (pin "P$2") (pinfunction "P$2_P$2") (pintype "bidirectional"))
      (node (ref "U$9") (pin "34") (pinfunction "SL_C_34") (pintype "bidirectional"))
      (node (ref "U$9") (pin "57") (pinfunction "GND_PAD_57") (pintype "bidirectional"))
      (node (ref "U1") (pin "2") (pinfunction "VSS_2") (pintype "bidirectional"))
      (node (ref "X1") (pin "2") (pinfunction "3_2") (pintype "passive"))
      (node (ref "X1") (pin "4") (pinfunction "3_4") (pintype "passive"))
    )
    (net (code "49") (name "HALL1") (class "Default")
      (node (ref "IC1") (pin "58") (pinfunction "PB6-I2C1SCL/TIM4CH1/CAN2TX/DCMID5/USART1TX_58") (pintype "bidirectional"))
      (node (ref "JP2") (pin "5") (pinfunction "5_5") (pintype "passive"))
      (node (ref "R19") (pin "2") (pinfunction "2_2") (pintype "passive"))
      (node (ref "TP31") (pin "TP") (pinfunction "TP_TP") (pintype "input"))
    )
    (net (code "50") (name "HALL2") (class "Default")
      (node (ref "IC1") (pin "59") (pinfunction "PB7-I2C1SDA/FSMCNL/DCMIVSYNC/USART1RX/TIM4CH2_59") (pintype "bidirectional"))
      (node (ref "JP2") (pin "4") (pinfunction "4_4") (pintype "passive"))
      (node (ref "R20") (pin "2") (pinfunction "2_2") (pintype "passive"))
      (node (ref "TP32") (pin "TP") (pinfunction "TP_TP") (pintype "input"))
    )
    (net (code "51") (name "HALL3") (class "Default")
      (node (ref "IC1") (pin "61") (pinfunction "PB8-TIM4CH3/SDIOD4/TIM10CH1/DCMID6/ETHTXD3/I2C1SCL/CAN1RX_61") (pintype "bidirectional"))
      (node (ref "JP2") (pin "3") (pinfunction "3_3") (pintype "passive"))
      (node (ref "R21") (pin "2") (pinfunction "2_2") (pintype "passive"))
      (node (ref "TP33") (pin "TP") (pinfunction "TP_TP") (pintype "input"))
    )
    (net (code "52") (name "Net-(C30-Pad2)") (class "Default")
      (node (ref "C30") (pin "2") (pinfunction "2_2") (pintype "passive"))
      (node (ref "R18") (pin "1") (pinfunction "1_1") (pintype "passive"))
    )
    (net (code "53") (name "Net-(D2-PadC)") (class "Default")
      (node (ref "D2") (pin "C") (pinfunction "C_C") (pintype "passive"))
      (node (ref "R24") (pin "2") (pinfunction "2_2") (pintype "passive"))
    )
    (net (code "54") (name "Net-(D3-PadC)") (class "Default")
      (node (ref "D3") (pin "C") (pinfunction "C_C") (pintype "passive"))
      (node (ref "R25") (pin "2") (pinfunction "2_2") (pintype "passive"))
    )
    (net (code "55") (name "Net-(D4-PadC)") (class "Default")
      (node (ref "D4") (pin "C") (pinfunction "C_C") (pintype "passive"))
      (node (ref "R33") (pin "2") (pinfunction "2_2") (pintype "passive"))
    )
    (net (code "56") (name "Net-(D5-PadC)") (class "Default")
      (node (ref "D5") (pin "C") (pinfunction "C_C") (pintype "passive"))
      (node (ref "R34") (pin "2") (pinfunction "2_2") (pintype "passive"))
    )
    (net (code "57") (name "Net-(D6-PadC)") (class "Default")
      (node (ref "D6") (pin "C") (pinfunction "C_C") (pintype "passive"))
      (node (ref "R37") (pin "2") (pinfunction "2_2") (pintype "passive"))
    )
    (net (code "58") (name "Net-(IC1-PC0-OTGSTP-ADC10)") (class "Default")
      (node (ref "D2") (pin "A") (pinfunction "A_A") (pintype "passive"))
      (node (ref "IC1") (pin "8") (pinfunction "PC0-OTGSTP-ADC10_8") (pintype "bidirectional"))
    )
    (net (code "59") (name "Net-(IC1-PC1-ETHMDC-ADC11)") (class "Default")
      (node (ref "D3") (pin "A") (pinfunction "A_A") (pintype "passive"))
      (node (ref "IC1") (pin "9") (pinfunction "PC1-ETHMDC-ADC11_9") (pintype "bidirectional"))
    )
    (net (code "60") (name "Net-(IC1-PC2-SPI2MISO{slash}OTGDIR{slash}ETHTXD2{slash}I2S2EXTSD-ADC12)") (class "Default")
      (node (ref "D4") (pin "A") (pinfunction "A_A") (pintype "passive"))
      (node (ref "IC1") (pin "10") (pinfunction "PC2-SPI2MISO/OTGDIR/ETHTXD2/I2S2EXTSD-ADC12_10") (pintype "bidirectional"))
    )
    (net (code "61") (name "Net-(IC1-PC3-SPI2MOSI{slash}I2S2SD{slash}OTGNXT{slash}ETHTXCLK-ADC13)") (class "Default")
      (node (ref "D5") (pin "A") (pinfunction "A_A") (pintype "passive"))
      (node (ref "IC1") (pin "11") (pinfunction "PC3-SPI2MOSI/I2S2SD/OTGNXT/ETHTXCLK-ADC13_11") (pintype "bidirectional"))
    )
    (net (code "62") (name "Net-(IC1-PH0{slash}OSCIN--OSCIN)") (class "Default")
      (node (ref "C38") (pin "2") (pinfunction "2_2") (pintype "passive"))
      (node (ref "IC1") (pin "5") (pinfunction "PH0/OSCIN--OSCIN_5") (pintype "input"))
      (node (ref "X1") (pin "3") (pinfunction "1_3") (pintype "passive"))
    )
    (net (code "63") (name "Net-(IC1-PH1{slash}OSCOUT--OSCOUT)") (class "Default")
      (node (ref "C37") (pin "2") (pinfunction "2_2") (pintype "passive"))
      (node (ref "IC1") (pin "6") (pinfunction "PH1/OSCOUT--OSCOUT_6") (pintype "output"))
      (node (ref "X1") (pin "1") (pinfunction "2_1") (pintype "passive"))
    )
    (net (code "64") (name "Net-(IC1-VCAP1)") (class "Default")
      (node (ref "C42") (pin "1") (pinfunction "1_1") (pintype "passive"))
      (node (ref "IC1") (pin "31") (pinfunction "VCAP1_31") (pintype "power_in"))
    )
    (net (code "65") (name "Net-(IC1-VCAP2)") (class "Default")
      (node (ref "C41") (pin "1") (pinfunction "1_1") (pintype "passive"))
      (node (ref "IC1") (pin "47") (pinfunction "VCAP2_47") (pintype "power_in"))
    )
    (net (code "66") (name "Net-(R1-Pad2)") (class "Default")
      (node (ref "R1") (pin "2") (pinfunction "2_2") (pintype "passive"))
      (node (ref "U$1") (pin "G") (pinfunction "G_G") (pintype "passive"))
    )
    (net (code "67") (name "Net-(R2-Pad2)") (class "Default")
      (node (ref "R2") (pin "2") (pinfunction "2_2") (pintype "passive"))
      (node (ref "U$2") (pin "G") (pinfunction "G_G") (pintype "passive"))
    )
    (net (code "68") (name "Net-(R3-Pad2)") (class "Default")
      (node (ref "R3") (pin "2") (pinfunction "2_2") (pintype "passive"))
      (node (ref "U$3") (pin "G") (pinfunction "G_G") (pintype "passive"))
    )
    (net (code "69") (name "Net-(R4-Pad2)") (class "Default")
      (node (ref "R4") (pin "2") (pinfunction "2_2") (pintype "passive"))
      (node (ref "U$4") (pin "G") (pinfunction "G_G") (pintype "passive"))
    )
    (net (code "70") (name "Net-(R5-Pad2)") (class "Default")
      (node (ref "R5") (pin "2") (pinfunction "2_2") (pintype "passive"))
      (node (ref "U$5") (pin "G") (pinfunction "G_G") (pintype "passive"))
    )
    (net (code "71") (name "Net-(R6-Pad2)") (class "Default")
      (node (ref "R6") (pin "2") (pinfunction "2_2") (pintype "passive"))
      (node (ref "U$6") (pin "G") (pinfunction "G_G") (pintype "passive"))
    )
    (net (code "72") (name "Net-(R7-Pad2)") (class "Default")
      (node (ref "R7") (pin "2") (pinfunction "2_2") (pintype "passive"))
      (node (ref "U$7") (pin "P$4") (pinfunction "P$4_P$4") (pintype "bidirectional"))
    )
    (net (code "73") (name "Net-(R8-Pad2)") (class "Default")
      (node (ref "R8") (pin "2") (pinfunction "2_2") (pintype "passive"))
      (node (ref "U$7") (pin "P$3") (pinfunction "P$3_P$3") (pintype "bidirectional"))
    )
    (net (code "74") (name "Net-(R9-Pad2)") (class "Default")
      (node (ref "R9") (pin "2") (pinfunction "2_2") (pintype "passive"))
      (node (ref "U$8") (pin "P$3") (pinfunction "P$3_P$3") (pintype "bidirectional"))
    )
    (net (code "75") (name "Net-(R10-Pad2)") (class "Default")
      (node (ref "R10") (pin "2") (pinfunction "2_2") (pintype "passive"))
      (node (ref "U$8") (pin "P$4") (pinfunction "P$4_P$4") (pintype "bidirectional"))
    )
    (net (code "76") (name "Net-(U$9-AVDD)") (class "Default")
      (node (ref "C8") (pin "1") (pinfunction "1_1") (pintype "passive"))
      (node (ref "U$9") (pin "27") (pinfunction "AVDD_27") (pintype "bidirectional"))
    )
    (net (code "77") (name "Net-(U$9-BST_A)") (class "Default")
      (node (ref "C3") (pin "1") (pinfunction "1_1") (pintype "passive"))
      (node (ref "U$9") (pin "48") (pinfunction "BST_A_48") (pintype "bidirectional"))
    )
    (net (code "78") (name "Net-(U$9-BST_B)") (class "Default")
      (node (ref "C4") (pin "1") (pinfunction "1_1") (pintype "passive"))
      (node (ref "U$9") (pin "43") (pinfunction "BST_B_43") (pintype "bidirectional"))
    )
    (net (code "79") (name "Net-(U$9-BST_BK)") (class "Default")
      (node (ref "C13") (pin "1") (pinfunction "1_1") (pintype "passive"))
      (node (ref "U$9") (pin "52") (pinfunction "BST_BK_52") (pintype "bidirectional"))
    )
    (net (code "80") (name "Net-(U$9-BST_C)") (class "Default")
      (node (ref "C5") (pin "1") (pinfunction "1_1") (pintype "passive"))
      (node (ref "U$9") (pin "38") (pinfunction "BST_C_38") (pintype "bidirectional"))
    )
    (net (code "81") (name "Net-(U$9-COMP)") (class "Default")
      (node (ref "C29") (pin "2") (pinfunction "2_2") (pintype "passive"))
      (node (ref "R18") (pin "2") (pinfunction "2_2") (pintype "passive"))
      (node (ref "U$9") (pin "2") (pinfunction "COMP_2") (pintype "bidirectional"))
    )
    (net (code "82") (name "Net-(U$9-CP1)") (class "Default")
      (node (ref "C6") (pin "2") (pinfunction "2_2") (pintype "passive"))
      (node (ref "U$9") (pin "14") (pinfunction "CP1_14") (pintype "bidirectional"))
    )
    (net (code "83") (name "Net-(U$9-CP2)") (class "Default")
      (node (ref "C6") (pin "1") (pinfunction "1_1") (pintype "passive"))
      (node (ref "U$9") (pin "15") (pinfunction "CP2_15") (pintype "bidirectional"))
    )
    (net (code "84") (name "Net-(U$9-DTC)") (class "Default")
      (node (ref "R14") (pin "1") (pinfunction "1_1") (pintype "passive"))
      (node (ref "U$9") (pin "7") (pinfunction "DTC_7") (pintype "bidirectional"))
    )
    (net (code "85") (name "Net-(U$9-DVDD)") (class "Default")
      (node (ref "C9") (pin "1") (pinfunction "1_1") (pintype "passive"))
      (node (ref "U$9") (pin "23") (pinfunction "DVDD_23") (pintype "bidirectional"))
    )
    (net (code "86") (name "Net-(U$9-GVDD)") (class "Default")
      (node (ref "C7") (pin "1") (pinfunction "1_1") (pintype "passive"))
      (node (ref "U$9") (pin "13") (pinfunction "GVDD_13") (pintype "bidirectional"))
    )
    (net (code "87") (name "Net-(U$9-PH_1)") (class "Default")
      (node (ref "C13") (pin "2") (pinfunction "2_2") (pintype "passive"))
      (node (ref "D1") (pin "C") (pinfunction "C_C") (pintype "passive"))
      (node (ref "L1") (pin "1") (pinfunction "1_1") (pintype "passive"))
      (node (ref "U$9") (pin "50") (pinfunction "PH_1_50") (pintype "bidirectional"))
      (node (ref "U$9") (pin "51") (pinfunction "PH_2_51") (pintype "bidirectional"))
    )
    (net (code "88") (name "Net-(U$9-RT_CLK)") (class "Default")
      (node (ref "R17") (pin "1") (pinfunction "1_1") (pintype "passive"))
      (node (ref "U$9") (pin "1") (pinfunction "RT_CLK_1") (pintype "bidirectional"))
    )
    (net (code "89") (name "Net-(U$9-SS_TR)") (class "Default")
      (node (ref "C12") (pin "2") (pinfunction "2_2") (pintype "passive"))
      (node (ref "U$9") (pin "56") (pinfunction "SS_TR_56") (pintype "bidirectional"))
    )
    (net (code "90") (name "Net-(U$9-VSENSE)") (class "Default")
      (node (ref "R15") (pin "2") (pinfunction "2_2") (pintype "passive"))
      (node (ref "R16") (pin "1") (pinfunction "1_1") (pintype "passive"))
      (node (ref "U$9") (pin "3") (pinfunction "VSENSE_3") (pintype "bidirectional"))
    )
    (net (code "91") (name "Net-(U$12-CANH)") (class "Default")
      (node (ref "R35") (pin "2") (pinfunction "2_2") (pintype "passive"))
      (node (ref "U$12") (pin "P$3") (pinfunction "CANH_P$3") (pintype "bidirectional"))
      (node (ref "U1") (pin "7") (pinfunction "CANH_7") (pintype "bidirectional"))
    )
    (net (code "92") (name "Net-(U$12-CANL)") (class "Default")
      (node (ref "R35") (pin "1") (pinfunction "1_1") (pintype "passive"))
      (node (ref "U$12") (pin "P$5") (pinfunction "CANL_P$5") (pintype "bidirectional"))
      (node (ref "U1") (pin "6") (pinfunction "CANL_6") (pintype "bidirectional"))
    )
    (net (code "93") (name "Net-(U1-RS)") (class "Default")
      (node (ref "R36") (pin "1") (pinfunction "1_1") (pintype "passive"))
      (node (ref "U1") (pin "8") (pinfunction "RS_8") (pintype "bidirectional"))
    )
    (net (code "94") (name "TEMP") (class "Default")
      (node (ref "C27") (pin "1") (pinfunction "1_1") (pintype "passive"))
      (node (ref "IC1") (pin "20") (pinfunction "PA4-SPI1NSS/SPI3NSS/USART2CK/DCMIHSYNC/OTGSOF/I2S3WS-ADC4/DAC1_20") (pintype "bidirectional"))
      (node (ref "R32") (pin "1") (pinfunction "1_1") (pintype "passive"))
      (node (ref "TP30") (pin "TP") (pinfunction "TP_TP") (pintype "input"))
      (node (ref "U$11") (pin "1") (pinfunction "1_1") (pintype "passive"))
    )
    (net (code "95") (name "VCC") (class "Default")
      (node (ref "C10") (pin "1") (pinfunction "1_1") (pintype "passive"))
      (node (ref "C17") (pin "1") (pinfunction "1_1") (pintype "passive"))
      (node (ref "C39") (pin "1") (pinfunction "1_1") (pintype "passive"))
      (node (ref "C40") (pin "1") (pinfunction "1_1") (pintype "passive"))
      (node (ref "C43") (pin "2") (pinfunction "2_2") (pintype "passive"))
      (node (ref "C44") (pin "2") (pinfunction "2_2") (pintype "passive"))
      (node (ref "C45") (pin "2") (pinfunction "2_2") (pintype "passive"))
      (node (ref "C46") (pin "2") (pinfunction "2_2") (pintype "passive"))
      (node (ref "C47") (pin "2") (pinfunction "2_2") (pintype "passive"))
      (node (ref "D6") (pin "A") (pinfunction "A_A") (pintype "passive"))
      (node (ref "IC1") (pin "1") (pinfunction "VBAT_1") (pintype "power_in"))
      (node (ref "IC1") (pin "13") (pinfunction "VDDA_13") (pintype "power_in"))
      (node (ref "IC1") (pin "19") (pinfunction "VDD1_19") (pintype "power_in"))
      (node (ref "IC1") (pin "32") (pinfunction "VDD2_32") (pintype "power_in"))
      (node (ref "IC1") (pin "48") (pinfunction "VDD3_48") (pintype "power_in"))
      (node (ref "IC1") (pin "64") (pinfunction "VDD4_64") (pintype "bidirectional"))
      (node (ref "J2") (pin "3") (pinfunction "3_3") (pintype "passive"))
      (node (ref "J4") (pin "3") (pinfunction "3_3") (pintype "passive"))
      (node (ref "JP2") (pin "2") (pinfunction "2_2") (pintype "passive"))
      (node (ref "JP3") (pin "1") (pinfunction "1_1") (pintype "passive"))
      (node (ref "JP4") (pin "1") (pinfunction "1_1") (pintype "passive"))
      (node (ref "L1") (pin "2") (pinfunction "2_2") (pintype "passive"))
      (node (ref "R11") (pin "1") (pinfunction "1_1") (pintype "passive"))
      (node (ref "R12") (pin "2") (pinfunction "2_2") (pintype "passive"))
      (node (ref "R13") (pin "2") (pinfunction "2_2") (pintype "passive"))
      (node (ref "R16") (pin "2") (pinfunction "2_2") (pintype "passive"))
      (node (ref "R19") (pin "1") (pinfunction "1_1") (pintype "passive"))
      (node (ref "R20") (pin "1") (pinfunction "1_1") (pintype "passive"))
      (node (ref "R21") (pin "1") (pinfunction "1_1") (pintype "passive"))
      (node (ref "U$10") (pin "1") (pinfunction "IN_1") (pintype "input"))
      (node (ref "U$11") (pin "2") (pinfunction "2_2") (pintype "passive"))
      (node (ref "U$9") (pin "49") (pinfunction "VDD_SPI_49") (pintype "bidirectional"))
    )
    (net (code "96") (name "VDD") (class "Default")
      (node (ref "C14") (pin "1") (pinfunction "1_1") (pintype "passive"))
      (node (ref "C15") (pin "1") (pinfunction "1_1") (pintype "passive"))
      (node (ref "C16") (pin "1") (pinfunction "1_1") (pintype "passive"))
      (node (ref "C18") (pin "1") (pinfunction "1_1") (pintype "passive"))
      (node (ref "C19") (pin "1") (pinfunction "1_1") (pintype "passive"))
      (node (ref "C20") (pin "1") (pinfunction "1_1") (pintype "passive"))
      (node (ref "C21") (pin "1") (pinfunction "1_1") (pintype "passive"))
      (node (ref "C22") (pin "1") (pinfunction "1_1") (pintype "passive"))
      (node (ref "C23") (pin "1") (pinfunction "1_1") (pintype "passive"))
      (node (ref "C24") (pin "1") (pinfunction "1_1") (pintype "passive"))
      (node (ref "C25") (pin "1") (pinfunction "1_1") (pintype "passive"))
      (node (ref "C26") (pin "1") (pinfunction "1_1") (pintype "passive"))
      (node (ref "C28") (pin "1") (pinfunction "1_1") (pintype "passive"))
      (node (ref "C31") (pin "1") (pinfunction "1_1") (pintype "passive"))
      (node (ref "C32") (pin "+") (pinfunction "+_+") (pintype "passive"))
      (node (ref "C33") (pin "+") (pinfunction "+_+") (pintype "passive"))
      (node (ref "C34") (pin "+") (pinfunction "+_+") (pintype "passive"))
      (node (ref "C35") (pin "+") (pinfunction "+_+") (pintype "passive"))
      (node (ref "IN_VDD") (pin "1") (pinfunction "IN_1") (pintype "bidirectional"))
      (node (ref "R22") (pin "1") (pinfunction "1_1") (pintype "passive"))
      (node (ref "U$1") (pin "D") (pinfunction "D_D") (pintype "passive"))
      (node (ref "U$3") (pin "D") (pinfunction "D_D") (pintype "passive"))
      (node (ref "U$5") (pin "D") (pinfunction "D_D") (pintype "passive"))
      (node (ref "U$9") (pin "29") (pinfunction "PVDD1_29") (pintype "bidirectional"))
      (node (ref "U$9") (pin "53") (pinfunction "PVDD2_1_53") (pintype "bidirectional"))
      (node (ref "U$9") (pin "54") (pinfunction "PVDD2_2_54") (pintype "bidirectional"))
    )
    (net (code "97") (name "VSENS_A") (class "Default")
      (node (ref "C49") (pin "1") (pinfunction "1_1") (pintype "passive"))
      (node (ref "IC1") (pin "14") (pinfunction "PA0-USART2CTS/USART4TX/ETHCRS/TIM2CH1ETR/TIM5CH1/TIM8ETR-ADC0/WKUP_14") (pintype "bidirectional"))
      (node (ref "R26") (pin "2") (pinfunction "2_2") (pintype "passive"))
      (node (ref "R27") (pin "2") (pinfunction "2_2") (pintype "passive"))
      (node (ref "TP34") (pin "TP") (pinfunction "TP_TP") (pintype "input"))
    )
    (net (code "98") (name "VSENS_B") (class "Default")
      (node (ref "C50") (pin "1") (pinfunction "1_1") (pintype "passive"))
      (node (ref "IC1") (pin "15") (pinfunction "PA1-USART2RTS/USART4RX/ETHREFCLK/ETHRXCLK/TIM5CH2/TIM2CH2-ADC1_15") (pintype "bidirectional"))
      (node (ref "R28") (pin "2") (pinfunction "2_2") (pintype "passive"))
      (node (ref "R29") (pin "2") (pinfunction "2_2") (pintype "passive"))
      (node (ref "TP35") (pin "TP") (pinfunction "TP_TP") (pintype "input"))
    )
    (net (code "99") (name "VSENS_BATT") (class "Default")
      (node (ref "C48") (pin "1") (pinfunction "1_1") (pintype "passive"))
      (node (ref "IC1") (pin "17") (pinfunction "PA3-USART2RX/TIM5CH4/TIM9CH2/TIM2CH4/OTGD0/ETHCOL-ADC3_17") (pintype "bidirectional"))
      (node (ref "R22") (pin "2") (pinfunction "2_2") (pintype "passive"))
      (node (ref "R23") (pin "2") (pinfunction "2_2") (pintype "passive"))
      (node (ref "TP37") (pin "TP") (pinfunction "TP_TP") (pintype "input"))
    )
    (net (code "100") (name "VSENS_C") (class "Default")
      (node (ref "C51") (pin "1") (pinfunction "1_1") (pintype "passive"))
      (node (ref "IC1") (pin "16") (pinfunction "PA2-USART2TX/TIM5CH3/TIM9CH1/TIM2CH3/ETHMDIO-ADC2_16") (pintype "bidirectional"))
      (node (ref "R30") (pin "2") (pinfunction "2_2") (pintype "passive"))
      (node (ref "R31") (pin "2") (pinfunction "2_2") (pintype "passive"))
      (node (ref "TP36") (pin "TP") (pinfunction "TP_TP") (pintype "input"))
    )
    (net (code "101") (name "unconnected-(IC1-PA7-SPI1MOSI{slash}TIM8CH1N{slash}TIM14CH1{slash}TIM3CH2{slash}ETHRXDV{slash}TIM1CH1N{slash}ETHCRSDV-ADC7-Pad23)") (class "Default")
      (node (ref "IC1") (pin "23") (pinfunction "PA7-SPI1MOSI/TIM8CH1N/TIM14CH1/TIM3CH2/ETHRXDV/TIM1CH1N/ETHCRSDV-ADC7_23") (pintype "bidirectional"))
    )
    (net (code "102") (name "unconnected-(IC1-PB2{slash}BOOT1-Pad28)") (class "Default")
      (node (ref "IC1") (pin "28") (pinfunction "PB2/BOOT1_28") (pintype "bidirectional"))
    )
    (net (code "103") (name "unconnected-(IC1-PB3{slash}JTDO{slash}TRACESWO-SPI3SCK{slash}I2S3CK{slash}TIM2CH2{slash}SPI1SCK-Pad55)") (class "Default")
      (node (ref "IC1") (pin "55") (pinfunction "PB3/JTDO/TRACESWO-SPI3SCK/I2S3CK/TIM2CH2/SPI1SCK_55") (pintype "bidirectional"))
    )
    (net (code "104") (name "unconnected-(IC1-PB4{slash}JNTRST-SPI3MISO{slash}TIM3CH1{slash}SPI1MISO{slash}I2S3EXTSD-Pad56)") (class "Default")
      (node (ref "IC1") (pin "56") (pinfunction "PB4/JNTRST-SPI3MISO/TIM3CH1/SPI1MISO/I2S3EXTSD_56") (pintype "bidirectional"))
    )
    (net (code "105") (name "unconnected-(IC1-PB5-I2C1SMBA{slash}CAN2RX{slash}OTGD7{slash}ETHPPSOUT{slash}TIM3CH2{slash}SPI1MOSI{slash}SPI3MOSI{slash}DCMID10{slash}I2S3SD-Pad57)") (class "Default")
      (node (ref "IC1") (pin "57") (pinfunction "PB5-I2C1SMBA/CAN2RX/OTGD7/ETHPPSOUT/TIM3CH2/SPI1MOSI/SPI3MOSI/DCMID10/I2S3SD_57") (pintype "bidirectional"))
    )
    (net (code "106") (name "unconnected-(IC1-PB9-SPI2NSS{slash}I2S2WS{slash}TIM4CH4{slash}TIM11CH1{slash}SDIOD5{slash}DCMID7{slash}I2C1SDA{slash}CAN1TX-Pad62)") (class "Default")
      (node (ref "IC1") (pin "62") (pinfunction "PB9-SPI2NSS/I2S2WS/TIM4CH4/TIM11CH1/SDIOD5/DCMID7/I2C1SDA/CAN1TX_62") (pintype "bidirectional"))
    )
    (net (code "107") (name "unconnected-(IC1-PC5-ETHRXD1-ADC15-Pad25)") (class "Default")
      (node (ref "IC1") (pin "25") (pinfunction "PC5-ETHRXD1-ADC15_25") (pintype "bidirectional"))
    )
    (net (code "108") (name "unconnected-(IC1-PC8-TIM8CH3{slash}SDIOD0{slash}TIM3CH3{slash}USART6CK{slash}DCMID2-Pad39)") (class "Default")
      (node (ref "IC1") (pin "39") (pinfunction "PC8-TIM8CH3/SDIOD0/TIM3CH3/USART6CK/DCMID2_39") (pintype "bidirectional"))
    )
    (net (code "109") (name "unconnected-(IC1-PC13--RTCO{slash}RTCTAMP1{slash}RTCTS-Pad2)") (class "Default")
      (node (ref "IC1") (pin "2") (pinfunction "PC13--RTCO/RTCTAMP1/RTCTS_2") (pintype "bidirectional"))
    )
    (net (code "110") (name "unconnected-(IC1-PC14{slash}OSC32IN--OSC32IN-Pad3)") (class "Default")
      (node (ref "IC1") (pin "3") (pinfunction "PC14/OSC32IN--OSC32IN_3") (pintype "bidirectional"))
    )
    (net (code "111") (name "unconnected-(IC1-PC15{slash}OSC32OUT--OSC32OUT-Pad4)") (class "Default")
      (node (ref "IC1") (pin "4") (pinfunction "PC15/OSC32OUT--OSC32OUT_4") (pintype "bidirectional"))
    )
    (net (code "112") (name "unconnected-(IC1-PD2-TIM3ETR{slash}UART5RX{slash}SDIOCMD{slash}DCMID11-Pad54)") (class "Default")
      (node (ref "IC1") (pin "54") (pinfunction "PD2-TIM3ETR/UART5RX/SDIOCMD/DCMID11_54") (pintype "bidirectional"))
    )
    (net (code "113") (name "unconnected-(JP3-Pad6)") (class "Default")
      (node (ref "JP3") (pin "6") (pinfunction "6_6") (pintype "passive"))
    )
    (net (code "114") (name "unconnected-(U$9-EN_BUCK-Pad55)") (class "Default")
      (node (ref "U$9") (pin "55") (pinfunction "EN_BUCK_55") (pintype "bidirectional"))
    )
    (net (code "115") (name "unconnected-(U$12-PadP$1)") (class "Default")
      (node (ref "U$12") (pin "P$1") (pinfunction "P$1_P$1") (pintype "bidirectional"))
    )
    (net (code "116") (name "unconnected-(U$12-PadP$6)") (class "Default")
      (node (ref "U$12") (pin "P$6") (pinfunction "P$6_P$6") (pintype "bidirectional"))
    )
    (net (code "117") (name "unconnected-(U1-VREF-Pad5)") (class "Default")
      (node (ref "U1") (pin "5") (pinfunction "VREF_5") (pintype "bidirectional"))
    )
  )
)
